# keyboard_main.net
KiCad netlist of a schematic drawn in Altium Designer
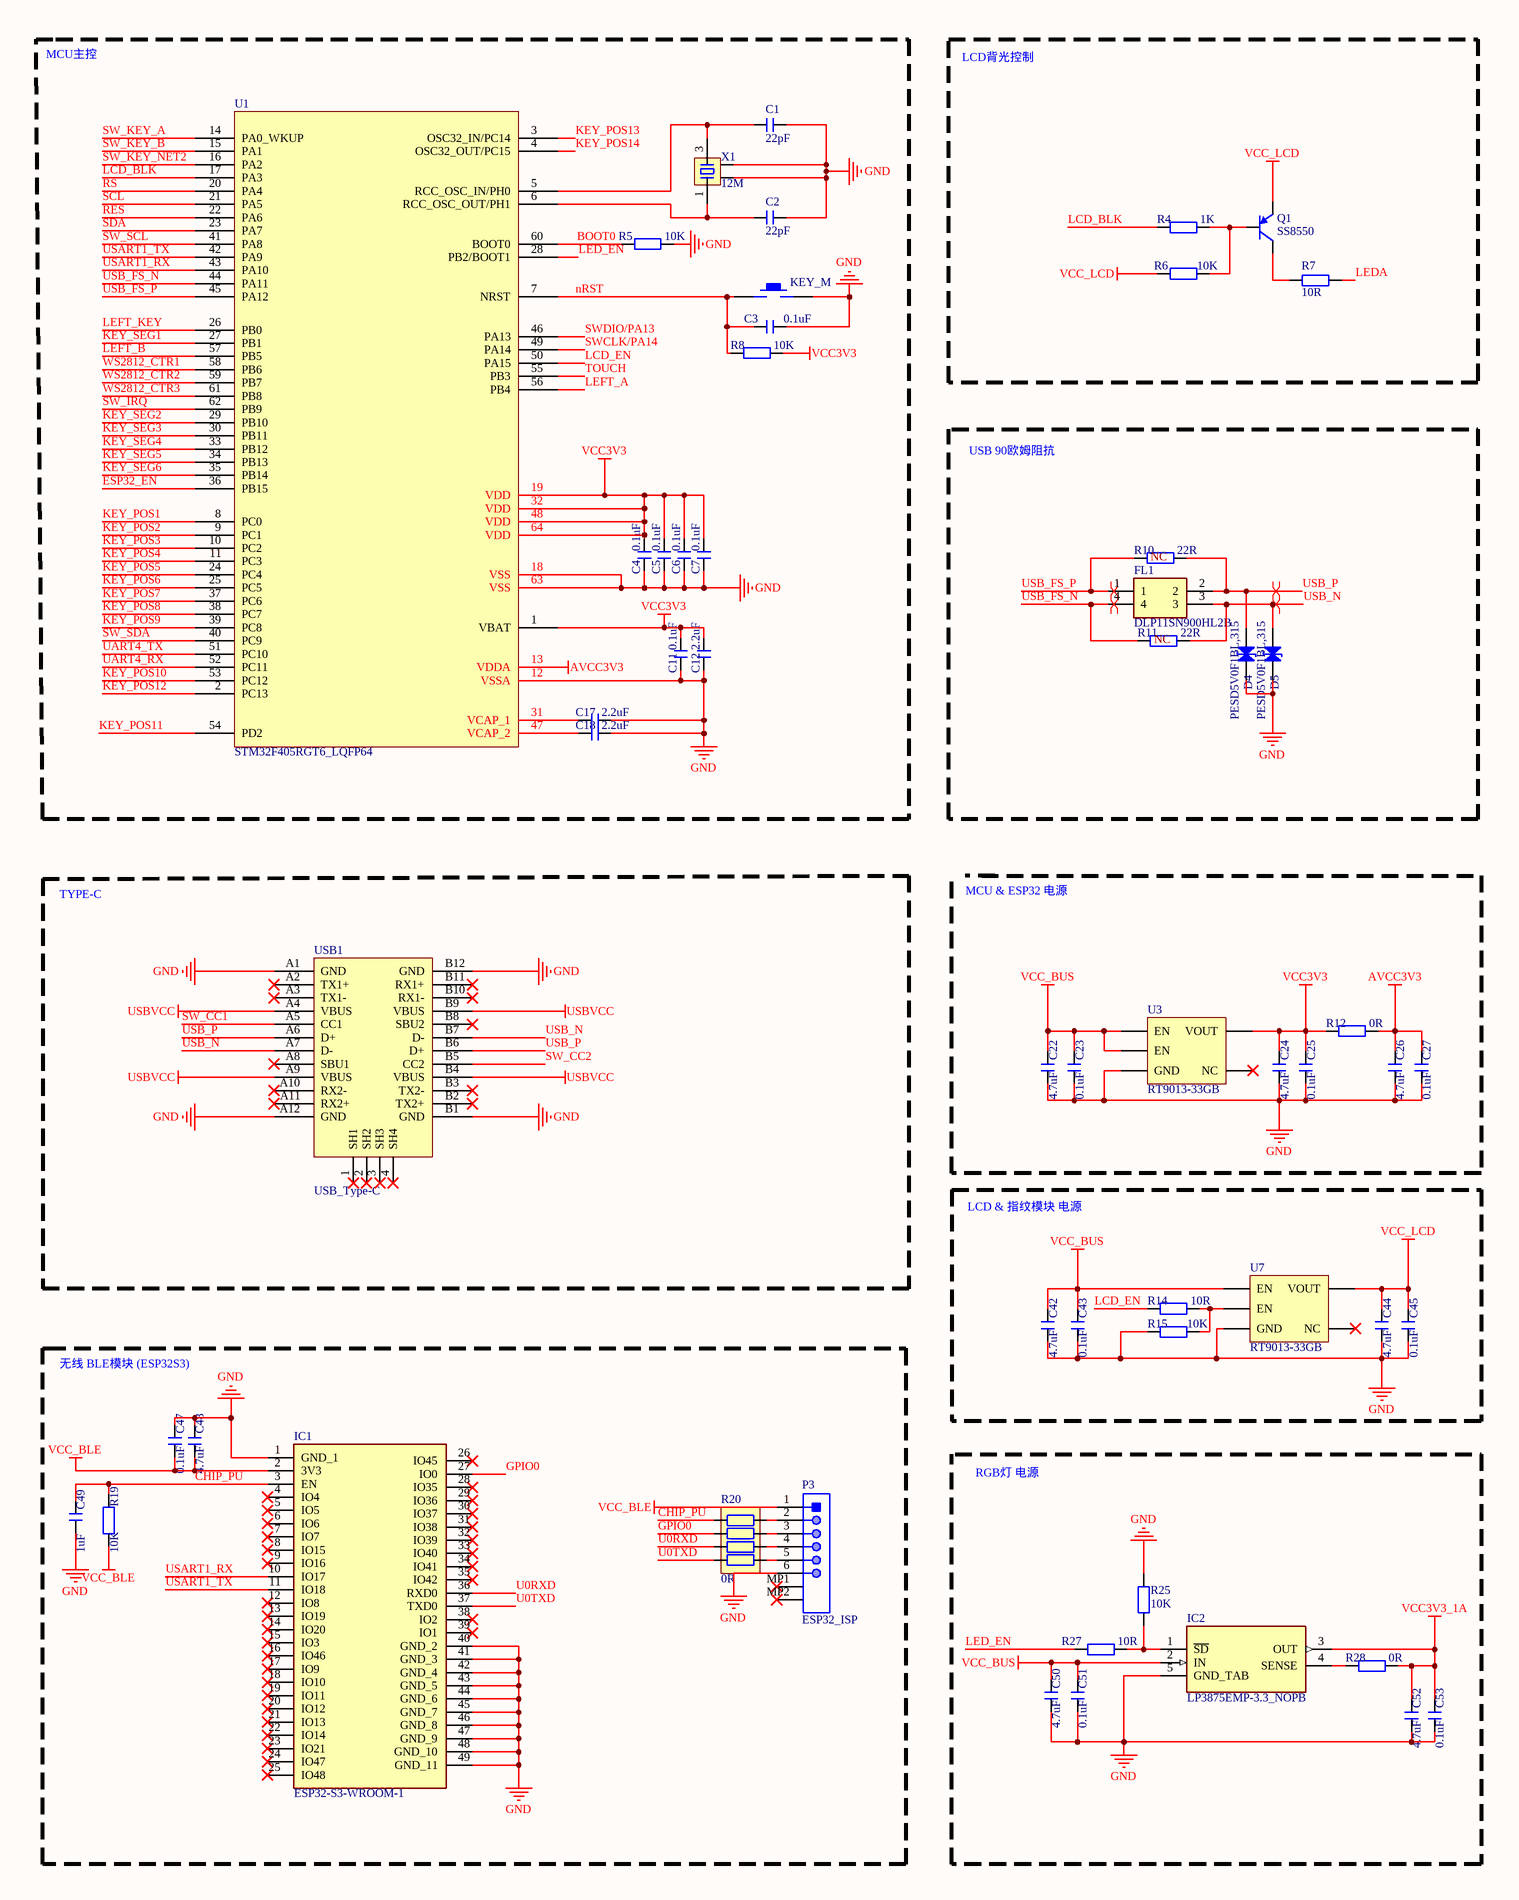
[diagram p0: keyboard_main.SchDoc, left]
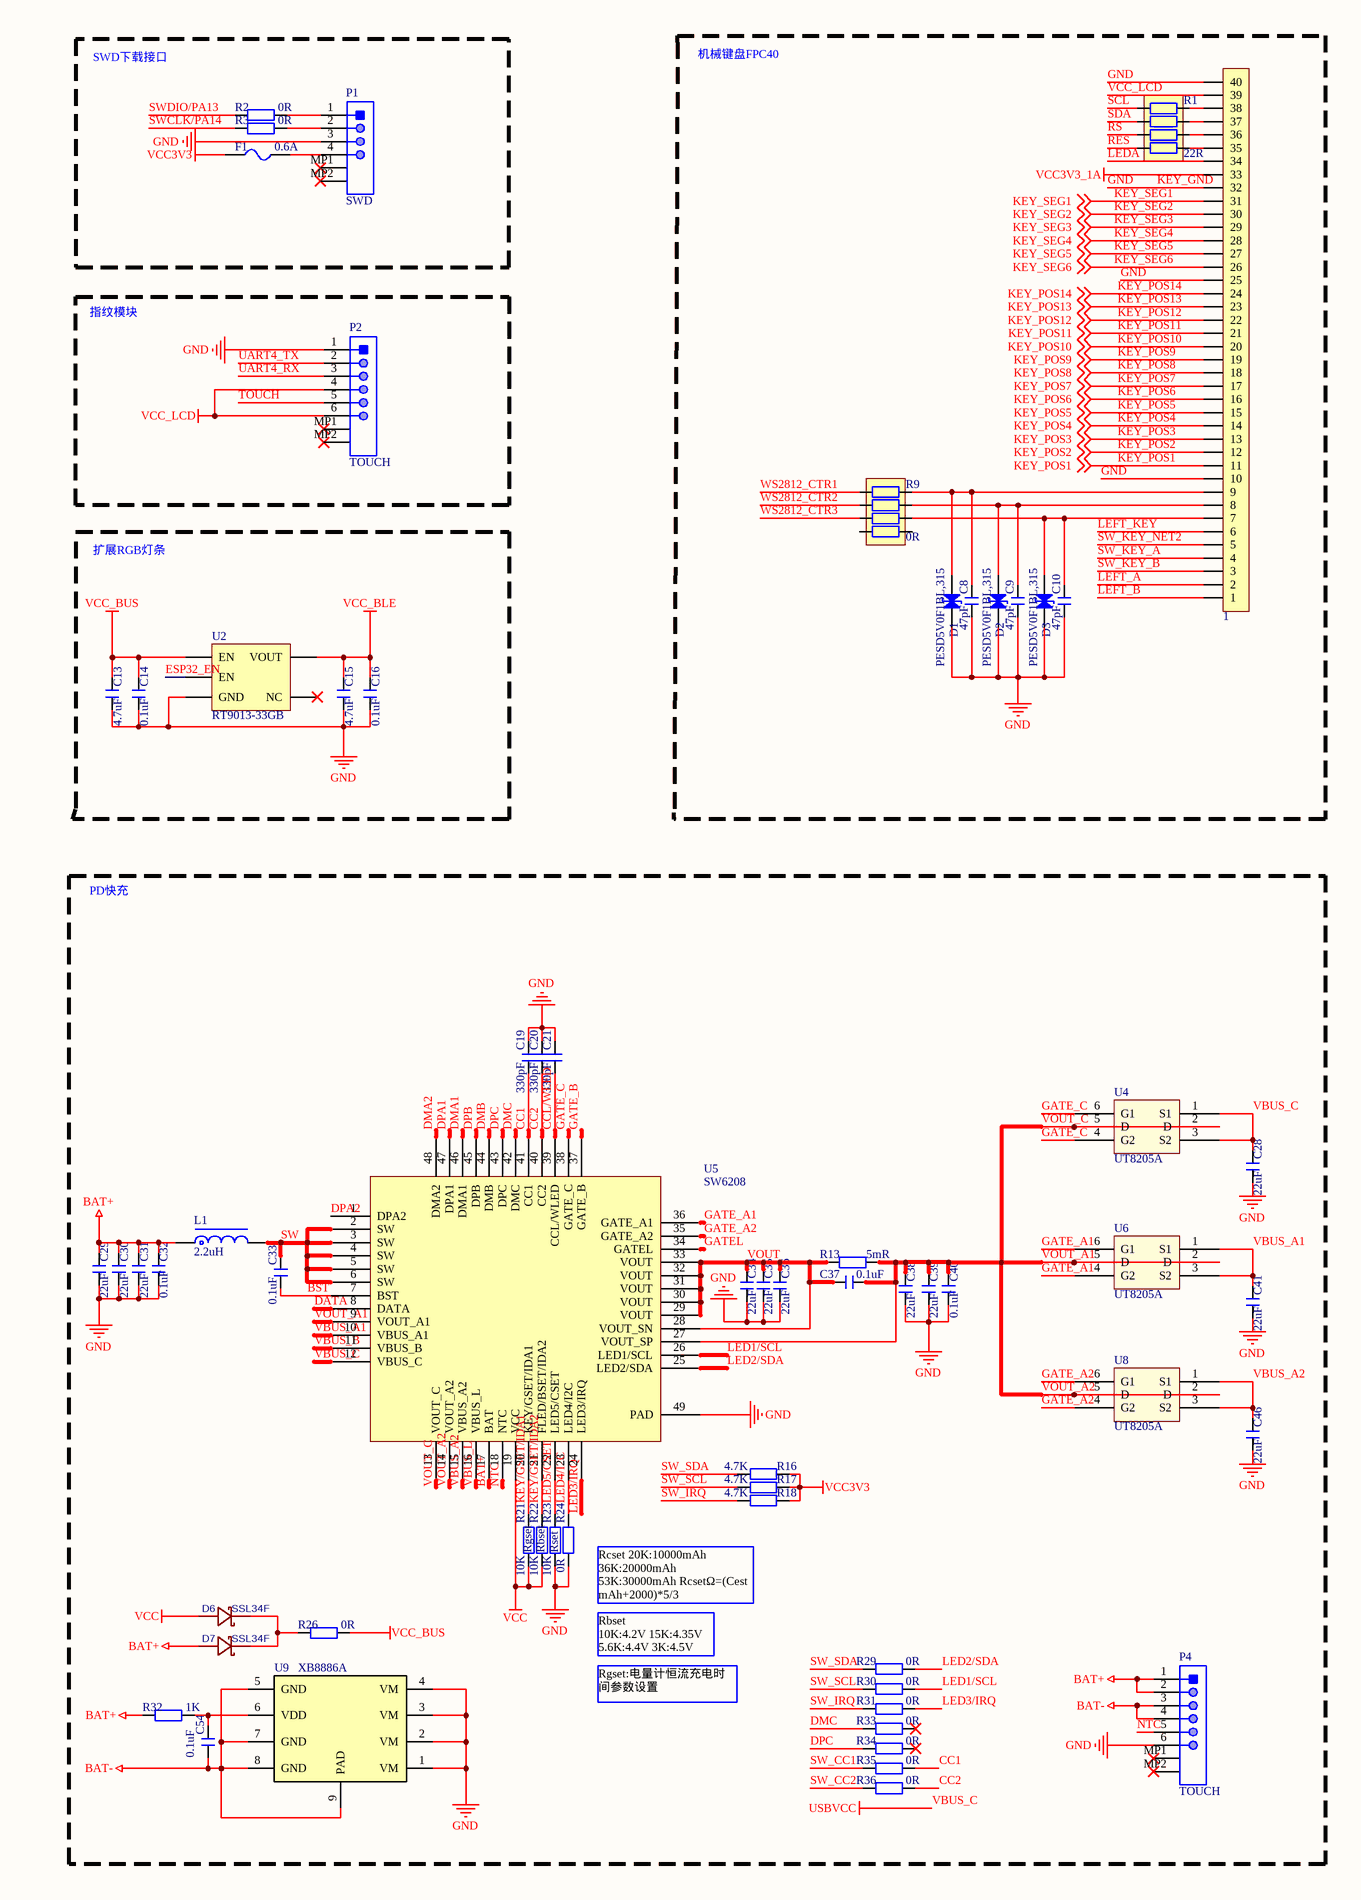
[diagram p1: keyboard_main.SchDoc, right]

(export (version "E")
  (design (tool "Eeschema 10.0.6"))
  (components
    (comp (ref "1")
      (value "FPC1.0-40P")
      (footprint "FPC0.5 2H-WS-40P")
      (description "FPC连接器")
      (fields (field (name "版权归属") "黎明电子style"))
      (libsource (lib "FPC连接器") (part "FPC-40P"))
    )
    (comp (ref "C1")
      (value "22pF")
      (footprint "C 0402_L")
      (description "贴片电容")
      (libsource (lib "0.1 - 电阻-电容-电感") (part "C"))
    )
    (comp (ref "C2")
      (value "22pF")
      (footprint "C 0402_L")
      (description "贴片电容")
      (libsource (lib "0.1 - 电阻-电容-电感") (part "C"))
    )
    (comp (ref "C3")
      (value "0.1uF")
      (footprint "C 0402_L")
      (description "贴片电容")
      (libsource (lib "0.1 - 电阻-电容-电感") (part "C"))
    )
    (comp (ref "C4")
      (value "0.1uF")
      (footprint "C 0402_L")
      (description "贴片电容")
      (libsource (lib "0.1 - 电阻-电容-电感") (part "C"))
    )
    (comp (ref "C5")
      (value "0.1uF")
      (footprint "C 0402_L")
      (description "贴片电容")
      (libsource (lib "0.1 - 电阻-电容-电感") (part "C"))
    )
    (comp (ref "C6")
      (value "0.1uF")
      (footprint "C 0402_L")
      (description "贴片电容")
      (libsource (lib "0.1 - 电阻-电容-电感") (part "C"))
    )
    (comp (ref "C7")
      (value "0.1uF")
      (footprint "C 0402_L")
      (description "贴片电容")
      (libsource (lib "0.1 - 电阻-电容-电感") (part "C"))
    )
    (comp (ref "C8")
      (value "47pF")
      (footprint "C 0402_L")
      (description "贴片电容")
      (libsource (lib "0.1 - 电阻-电容-电感") (part "C"))
    )
    (comp (ref "C9")
      (value "47pF")
      (footprint "C 0402_L")
      (description "贴片电容")
      (libsource (lib "0.1 - 电阻-电容-电感") (part "C"))
    )
    (comp (ref "C10")
      (value "47pF")
      (footprint "C 0402_L")
      (description "贴片电容")
      (libsource (lib "0.1 - 电阻-电容-电感") (part "C"))
    )
    (comp (ref "C11")
      (value "0.1uF")
      (footprint "C 0402_L")
      (description "贴片电容")
      (libsource (lib "0.1 - 电阻-电容-电感") (part "C"))
    )
    (comp (ref "C12")
      (value "2.2uF")
      (footprint "C 0402_L")
      (description "贴片电容")
      (libsource (lib "0.1 - 电阻-电容-电感") (part "C"))
    )
    (comp (ref "C13")
      (value "4.7uF")
      (footprint "C 0402_L")
      (description "贴片电容")
      (libsource (lib "0.1 - 电阻-电容-电感") (part "C"))
    )
    (comp (ref "C14")
      (value "0.1uF")
      (footprint "C 0402_L")
      (description "贴片电容")
      (libsource (lib "0.1 - 电阻-电容-电感") (part "C"))
    )
    (comp (ref "C15")
      (value "4.7uF")
      (footprint "C 0402_L")
      (description "贴片电容")
      (libsource (lib "0.1 - 电阻-电容-电感") (part "C"))
    )
    (comp (ref "C16")
      (value "0.1uF")
      (footprint "C 0402_L")
      (description "贴片电容")
      (libsource (lib "0.1 - 电阻-电容-电感") (part "C"))
    )
    (comp (ref "C17")
      (value "2.2uF")
      (footprint "C 0402_L")
      (description "贴片电容")
      (libsource (lib "0.1 - 电阻-电容-电感") (part "C"))
    )
    (comp (ref "C18")
      (value "2.2uF")
      (footprint "C 0402_L")
      (description "贴片电容")
      (libsource (lib "0.1 - 电阻-电容-电感") (part "C"))
    )
    (comp (ref "C19")
      (value "330pF")
      (footprint "C 0402_L")
      (description "贴片电容")
      (libsource (lib "0.1 - 电阻-电容-电感") (part "C"))
    )
    (comp (ref "C20")
      (value "330pF")
      (footprint "C 0402_L")
      (description "贴片电容")
      (libsource (lib "0.1 - 电阻-电容-电感") (part "C"))
    )
    (comp (ref "C21")
      (value "330pF")
      (footprint "C 0402_L")
      (description "贴片电容")
      (libsource (lib "0.1 - 电阻-电容-电感") (part "C"))
    )
    (comp (ref "C22")
      (value "4.7uF")
      (footprint "C 0402_L")
      (description "贴片电容")
      (libsource (lib "0.1 - 电阻-电容-电感") (part "C"))
    )
    (comp (ref "C23")
      (value "0.1uF")
      (footprint "C 0402_L")
      (description "贴片电容")
      (libsource (lib "0.1 - 电阻-电容-电感") (part "C"))
    )
    (comp (ref "C24")
      (value "4.7uF")
      (footprint "C 0402_L")
      (description "贴片电容")
      (libsource (lib "0.1 - 电阻-电容-电感") (part "C"))
    )
    (comp (ref "C25")
      (value "0.1uF")
      (footprint "C 0402_L")
      (description "贴片电容")
      (libsource (lib "0.1 - 电阻-电容-电感") (part "C"))
    )
    (comp (ref "C26")
      (value "4.7uF")
      (footprint "C 0402_L")
      (description "贴片电容")
      (libsource (lib "0.1 - 电阻-电容-电感") (part "C"))
    )
    (comp (ref "C27")
      (value "0.1uF")
      (footprint "C 0402_L")
      (description "贴片电容")
      (libsource (lib "0.1 - 电阻-电容-电感") (part "C"))
    )
    (comp (ref "C28")
      (value "22uF")
      (footprint "C 0805_L")
      (description "贴片电容")
      (libsource (lib "0.1 - 电阻-电容-电感") (part "C"))
    )
    (comp (ref "C29")
      (value "22uF")
      (footprint "C 0805_L")
      (description "贴片电容")
      (libsource (lib "0.1 - 电阻-电容-电感") (part "C"))
    )
    (comp (ref "C30")
      (value "22uF")
      (footprint "C 0805_L")
      (description "贴片电容")
      (libsource (lib "0.1 - 电阻-电容-电感") (part "C"))
    )
    (comp (ref "C31")
      (value "22uF")
      (footprint "C 0805_L")
      (description "贴片电容")
      (libsource (lib "0.1 - 电阻-电容-电感") (part "C"))
    )
    (comp (ref "C32")
      (value "0.1uF")
      (footprint "C 0805_L")
      (description "贴片电容")
      (libsource (lib "0.1 - 电阻-电容-电感") (part "C"))
    )
    (comp (ref "C33")
      (value "0.1uF")
      (footprint "C 0603_L")
      (description "贴片电容")
      (libsource (lib "0.1 - 电阻-电容-电感") (part "C"))
    )
    (comp (ref "C34")
      (value "22uF")
      (footprint "C 0805_L")
      (description "贴片电容")
      (libsource (lib "0.1 - 电阻-电容-电感") (part "C"))
    )
    (comp (ref "C35")
      (value "22uF")
      (footprint "C 0805_L")
      (description "贴片电容")
      (libsource (lib "0.1 - 电阻-电容-电感") (part "C"))
    )
    (comp (ref "C36")
      (value "22uF")
      (footprint "C 0805_L")
      (description "贴片电容")
      (libsource (lib "0.1 - 电阻-电容-电感") (part "C"))
    )
    (comp (ref "C37")
      (value "0.1uF")
      (footprint "C 0805_L")
      (description "贴片电容")
      (libsource (lib "0.1 - 电阻-电容-电感") (part "C"))
    )
    (comp (ref "C38")
      (value "22uF")
      (footprint "C 0805_L")
      (description "贴片电容")
      (libsource (lib "0.1 - 电阻-电容-电感") (part "C"))
    )
    (comp (ref "C39")
      (value "22uF")
      (footprint "C 0805_L")
      (description "贴片电容")
      (libsource (lib "0.1 - 电阻-电容-电感") (part "C"))
    )
    (comp (ref "C40")
      (value "0.1uF")
      (footprint "C 0805_L")
      (description "贴片电容")
      (libsource (lib "0.1 - 电阻-电容-电感") (part "C"))
    )
    (comp (ref "C41")
      (value "22uF")
      (footprint "C 0805_L")
      (description "贴片电容")
      (libsource (lib "0.1 - 电阻-电容-电感") (part "C"))
    )
    (comp (ref "C42")
      (value "4.7uF")
      (footprint "C 0402_L")
      (description "贴片电容")
      (libsource (lib "0.1 - 电阻-电容-电感") (part "C"))
    )
    (comp (ref "C43")
      (value "0.1uF")
      (footprint "C 0402_L")
      (description "贴片电容")
      (libsource (lib "0.1 - 电阻-电容-电感") (part "C"))
    )
    (comp (ref "C44")
      (value "4.7uF")
      (footprint "C 0402_L")
      (description "贴片电容")
      (libsource (lib "0.1 - 电阻-电容-电感") (part "C"))
    )
    (comp (ref "C45")
      (value "0.1uF")
      (footprint "C 0402_L")
      (description "贴片电容")
      (libsource (lib "0.1 - 电阻-电容-电感") (part "C"))
    )
    (comp (ref "C46")
      (value "22uF")
      (footprint "C 0805_L")
      (description "贴片电容")
      (libsource (lib "0.1 - 电阻-电容-电感") (part "C"))
    )
    (comp (ref "C47")
      (value "0.1uF")
      (footprint "C 0402_L")
      (description "贴片电容")
      (libsource (lib "0.1 - 电阻-电容-电感") (part "C"))
    )
    (comp (ref "C48")
      (value "4.7uF")
      (footprint "C 0402_L")
      (description "贴片电容")
      (libsource (lib "0.1 - 电阻-电容-电感") (part "C"))
    )
    (comp (ref "C49")
      (value "1uF")
      (footprint "C 0402_L")
      (description "贴片电容")
      (libsource (lib "0.1 - 电阻-电容-电感") (part "C"))
    )
    (comp (ref "C50")
      (value "4.7uF")
      (footprint "C 0402_L")
      (description "贴片电容")
      (libsource (lib "0.1 - 电阻-电容-电感") (part "C"))
    )
    (comp (ref "C51")
      (value "0.1uF")
      (footprint "C 0402_L")
      (description "贴片电容")
      (libsource (lib "0.1 - 电阻-电容-电感") (part "C"))
    )
    (comp (ref "C52")
      (value "4.7uF")
      (footprint "C 0402_L")
      (description "贴片电容")
      (libsource (lib "0.1 - 电阻-电容-电感") (part "C"))
    )
    (comp (ref "C53")
      (value "0.1uF")
      (footprint "C 0402_L")
      (description "贴片电容")
      (libsource (lib "0.1 - 电阻-电容-电感") (part "C"))
    )
    (comp (ref "C54")
      (value "0.1uF")
      (footprint "C 0805_L")
      (description "贴片电容")
      (libsource (lib "0.1 - 电阻-电容-电感") (part "C"))
    )
    (comp (ref "D1")
      (value "PESD5V0F1BL,315")
      (footprint "SOD-882_L1.0-W0.6-BI")
      (description "PESD5V0F1BL,315、ESD二极管、5.5V")
      (libsource (lib "0.2 -  二极管-整流桥") (part "PESD5V0F1BL,315"))
    )
    (comp (ref "D2")
      (value "PESD5V0F1BL,315")
      (footprint "SOD-882_L1.0-W0.6-BI")
      (description "PESD5V0F1BL,315、ESD二极管、5.5V")
      (libsource (lib "0.2 -  二极管-整流桥") (part "PESD5V0F1BL,315"))
    )
    (comp (ref "D3")
      (value "PESD5V0F1BL,315")
      (footprint "SOD-882_L1.0-W0.6-BI")
      (description "PESD5V0F1BL,315、ESD二极管、5.5V")
      (libsource (lib "0.2 -  二极管-整流桥") (part "PESD5V0F1BL,315"))
    )
    (comp (ref "D4")
      (value "PESD5V0F1BL,315")
      (footprint "SOD-882_L1.0-W0.6-BI")
      (description "PESD5V0F1BL,315、ESD二极管、5.5V")
      (libsource (lib "0.2 -  二极管-整流桥") (part "PESD5V0F1BL,315"))
    )
    (comp (ref "D5")
      (value "PESD5V0F1BL,315")
      (footprint "SOD-882_L1.0-W0.6-BI")
      (description "PESD5V0F1BL,315、ESD二极管、5.5V")
      (libsource (lib "0.2 -  二极管-整流桥") (part "PESD5V0F1BL,315"))
    )
    (comp (ref "D6")
      (value "SSL34F")
      (footprint "SMAF_L3.5-W2.6-LS4.7-RD")
      (fields (field (name "BOM_SUPPLIER PART") "C1884559") (field (name "CONTRIBUTOR") "LCSC"))
      (libsource (lib "mx_pcb_library") (part "SSL34F_C1884559"))
    )
    (comp (ref "D7")
      (value "SSL34F")
      (footprint "SMAF_L3.5-W2.6-LS4.7-RD")
      (fields (field (name "BOM_SUPPLIER PART") "C1884559") (field (name "CONTRIBUTOR") "LCSC"))
      (libsource (lib "mx_pcb_library") (part "SSL34F_C1884559"))
    )
    (comp (ref "F1")
      (value "0.6A")
      (footprint "FU 0402")
      (description "贴片保险丝")
      (libsource (lib "2.0 - 保险丝-晶振-光耦") (part "FU"))
    )
    (comp (ref "FL1")
      (value "DLP11SN900HL2B")
      (footprint "vSeasky:DLP11SA350HL2B")
      (description "Filter")
      (fields (field (name "MOUSER PART NUMBER") "81-DLP11SN900HL2B"))
      (libsource (lib "vSeasky") (part "DLP11SN900HL2B"))
    )
    (comp (ref "IC1")
      (value "ESP32-S3-WROOM-1")
      (footprint "mx_pcb_library:ESP32S3WROOM1")
      (description "Integrated Circuit")
      (libsource (lib "mx_pcb_library") (part "ESP32-S3-WROOM-1"))
    )
    (comp (ref "IC2")
      (value "LP3875EMP-3.3_NOPB")
      (footprint "mx_pcb_library:SOT150P700X180-5N")
      (description "Integrated Circuit")
      (fields
        (field (name "MANUFACTURER_PART_NUMBER") "LP3875EMP-3.3/NOPB")
        (field (name "MOUSER PART NUMBER") "926-LP3875EMP33NOPB")
      )
      (libsource (lib "mx_pcb_library") (part "LP3875EMP-3.3_NOPB"))
    )
    (comp (ref "L1")
      (value "2.2uH")
      (footprint "CD32")
      (description "CD系列贴片线绕功率电感")
      (libsource (lib "0.1 - 电阻-电容-电感") (part "L-SMD"))
    )
    (comp (ref "P1")
      (value "SWD")
      (footprint "JST-SM04B-SRSS-TB_V")
      (description "Male Header, Pitch 1 mm, 1 x 4 Position, Height 2.9 mm, -25 to 85 degC, RoHS, Tape and Reel")
      (fields (field (name "MANUFACTURER") "JST"))
      (libsource (lib "JST SH Connector") (part "SM04B-SRSS-TB(LF)(SN)"))
    )
    (comp (ref "P2")
      (value "TOUCH")
      (footprint "JST-SM06B-SRSS-TB_V")
      (description "Male Header, Pitch 1 mm, 1 x 6 Position, Height 2.9 mm, -25 to 85 degC, RoHS, Tape and Reel")
      (fields (field (name "MANUFACTURER") "JST"))
      (libsource (lib "JST SH Connector") (part "SM06B-SRSS-TB(LF)(SN)"))
    )
    (comp (ref "P3")
      (value "ESP32_ISP")
      (footprint "JST-SM06B-SRSS-TB_V")
      (description "Male Header, Pitch 1 mm, 1 x 6 Position, Height 2.9 mm, -25 to 85 degC, RoHS, Tape and Reel")
      (fields (field (name "MANUFACTURER") "JST"))
      (libsource (lib "JST SH Connector") (part "SM06B-SRSS-TB(LF)(SN)"))
    )
    (comp (ref "P4")
      (value "TOUCH")
      (footprint "JST-SM06B-SRSS-TB_V")
      (description "Male Header, Pitch 1 mm, 1 x 6 Position, Height 2.9 mm, -25 to 85 degC, RoHS, Tape and Reel")
      (fields (field (name "MANUFACTURER") "JST"))
      (libsource (lib "JST SH Connector") (part "SM06B-SRSS-TB(LF)(SN)"))
    )
    (comp (ref "Q1")
      (value "SS8550")
      (footprint "SOT23-3N")
      (description "高频放大-PNP型")
      (libsource (lib "0.4 - 三极管") (part "8550-SMD"))
    )
    (comp (ref "R1")
      (value "22R")
      (footprint "RCA-8P4R-0402")
      (description "贴片排阻")
      (libsource (lib "") (part "R-8P4R_1"))
    )
    (comp (ref "R2")
      (value "0R")
      (footprint "R 0402_L")
      (description "贴片电阻")
      (libsource (lib "0.1 - 电阻-电容-电感") (part "R"))
    )
    (comp (ref "R3")
      (value "0R")
      (footprint "R 0402_L")
      (description "贴片电阻")
      (libsource (lib "0.1 - 电阻-电容-电感") (part "R"))
    )
    (comp (ref "R4")
      (value "1K")
      (footprint "R 0402_L")
      (description "贴片电阻")
      (libsource (lib "0.1 - 电阻-电容-电感") (part "R"))
    )
    (comp (ref "R5")
      (value "10K")
      (footprint "R 0402_L")
      (description "贴片电阻")
      (libsource (lib "0.1 - 电阻-电容-电感") (part "R"))
    )
    (comp (ref "R6")
      (value "10K")
      (footprint "R 0402_L")
      (description "贴片电阻")
      (libsource (lib "0.1 - 电阻-电容-电感") (part "R"))
    )
    (comp (ref "R7")
      (value "10R")
      (footprint "R 0402_L")
      (description "贴片电阻")
      (libsource (lib "0.1 - 电阻-电容-电感") (part "R"))
    )
    (comp (ref "R8")
      (value "10K")
      (footprint "R 0402_L")
      (description "贴片电阻")
      (libsource (lib "0.1 - 电阻-电容-电感") (part "R"))
    )
    (comp (ref "R9")
      (value "0R")
      (footprint "RCA-8P4R-0402")
      (description "贴片排阻")
      (libsource (lib "") (part "R-8P4R_1"))
    )
    (comp (ref "R10")
      (value "22R")
      (footprint "R 0402_L")
      (description "贴片电阻")
      (libsource (lib "0.1 - 电阻-电容-电感") (part "R"))
    )
    (comp (ref "R11")
      (value "22R")
      (footprint "R 0402_L")
      (description "贴片电阻")
      (libsource (lib "0.1 - 电阻-电容-电感") (part "R"))
    )
    (comp (ref "R12")
      (value "0R")
      (footprint "R 0402_L")
      (description "贴片电阻")
      (libsource (lib "0.1 - 电阻-电容-电感") (part "R"))
    )
    (comp (ref "R13")
      (value "5mR")
      (footprint "R 1206_L")
      (description "贴片电阻")
      (libsource (lib "0.1 - 电阻-电容-电感") (part "R"))
    )
    (comp (ref "R14")
      (value "10R")
      (footprint "R 0402_L")
      (description "贴片电阻")
      (libsource (lib "0.1 - 电阻-电容-电感") (part "R"))
    )
    (comp (ref "R15")
      (value "10K")
      (footprint "R 0402_L")
      (description "贴片电阻")
      (libsource (lib "0.1 - 电阻-电容-电感") (part "R"))
    )
    (comp (ref "R16")
      (value "4.7K")
      (footprint "R 0402_L")
      (description "贴片电阻")
      (libsource (lib "0.1 - 电阻-电容-电感") (part "R"))
    )
    (comp (ref "R17")
      (value "4.7K")
      (footprint "R 0402_L")
      (description "贴片电阻")
      (libsource (lib "0.1 - 电阻-电容-电感") (part "R"))
    )
    (comp (ref "R18")
      (value "4.7K")
      (footprint "R 0402_L")
      (description "贴片电阻")
      (libsource (lib "0.1 - 电阻-电容-电感") (part "R"))
    )
    (comp (ref "R19")
      (value "10K")
      (footprint "R 0402_L")
      (description "贴片电阻")
      (libsource (lib "0.1 - 电阻-电容-电感") (part "R"))
    )
    (comp (ref "R20")
      (value "0R")
      (footprint "RCA-8P4R-0402")
      (description "贴片排阻")
      (libsource (lib "0.1 - 电阻-电容-电感") (part "R-8P4R"))
    )
    (comp (ref "R21")
      (value "10K")
      (footprint "R 0402_L")
      (description "贴片电阻")
      (libsource (lib "0.1 - 电阻-电容-电感") (part "R"))
    )
    (comp (ref "R22")
      (value "10K")
      (footprint "R 0402_L")
      (description "贴片电阻")
      (libsource (lib "0.1 - 电阻-电容-电感") (part "R"))
    )
    (comp (ref "R23")
      (value "10K")
      (footprint "R 0402_L")
      (description "贴片电阻")
      (libsource (lib "0.1 - 电阻-电容-电感") (part "R"))
    )
    (comp (ref "R24")
      (value "0R")
      (footprint "R 0402_L")
      (description "贴片电阻")
      (libsource (lib "0.1 - 电阻-电容-电感") (part "R"))
    )
    (comp (ref "R25")
      (value "10K")
      (footprint "R 0402_L")
      (description "贴片电阻")
      (libsource (lib "0.1 - 电阻-电容-电感") (part "R"))
    )
    (comp (ref "R26")
      (value "0R")
      (footprint "R 0402_L")
      (description "贴片电阻")
      (libsource (lib "0.1 - 电阻-电容-电感") (part "R"))
    )
    (comp (ref "R27")
      (value "10R")
      (footprint "R 0402_L")
      (description "贴片电阻")
      (libsource (lib "0.1 - 电阻-电容-电感") (part "R"))
    )
    (comp (ref "R28")
      (value "0R")
      (footprint "R 0402_L")
      (description "贴片电阻")
      (libsource (lib "0.1 - 电阻-电容-电感") (part "R"))
    )
    (comp (ref "R29")
      (value "0R")
      (footprint "R 0402_L")
      (description "贴片电阻")
      (libsource (lib "0.1 - 电阻-电容-电感") (part "R"))
    )
    (comp (ref "R30")
      (value "0R")
      (footprint "R 0402_L")
      (description "贴片电阻")
      (libsource (lib "0.1 - 电阻-电容-电感") (part "R"))
    )
    (comp (ref "R31")
      (value "0R")
      (footprint "R 0402_L")
      (description "贴片电阻")
      (libsource (lib "0.1 - 电阻-电容-电感") (part "R"))
    )
    (comp (ref "R32")
      (value "1K")
      (footprint "R 0402_L")
      (description "贴片电阻")
      (libsource (lib "0.1 - 电阻-电容-电感") (part "R"))
    )
    (comp (ref "R33")
      (value "0R")
      (footprint "R 0402_L")
      (description "贴片电阻")
      (libsource (lib "0.1 - 电阻-电容-电感") (part "R"))
    )
    (comp (ref "R34")
      (value "0R")
      (footprint "R 0402_L")
      (description "贴片电阻")
      (libsource (lib "0.1 - 电阻-电容-电感") (part "R"))
    )
    (comp (ref "R35")
      (value "0R")
      (footprint "R 0402_L")
      (description "贴片电阻")
      (libsource (lib "0.1 - 电阻-电容-电感") (part "R"))
    )
    (comp (ref "R36")
      (value "0R")
      (footprint "R 0402_L")
      (description "贴片电阻")
      (libsource (lib "0.1 - 电阻-电容-电感") (part "R"))
    )
    (comp (ref "RST1")
      (value "KEY_M")
      (footprint "SMD-3.2*4.2")
      (libsource (lib "mx_pcb_library") (part "KEY_M"))
    )
    (comp (ref "U1")
      (value "STM32F405RGT6_LQFP64")
      (footprint "LQFP-64_10X10X05P")
      (libsource (lib "mx_pcb_library") (part "STM32F405RGT6_LQFP64"))
    )
    (comp (ref "U2")
      (value "RT9013-33GB")
      (footprint "SOT23-5M")
      (libsource (lib "mx_pcb_library") (part "RT9013-33GB"))
    )
    (comp (ref "U3")
      (value "RT9013-33GB")
      (footprint "SOT23-5M")
      (libsource (lib "mx_pcb_library") (part "RT9013-33GB"))
    )
    (comp (ref "U4")
      (value "UT8205A")
      (footprint "mx_pcb_library:SOT23-6")
      (libsource (lib "mx_pcb_library") (part "UT8205A"))
    )
    (comp (ref "U5")
      (value "SW6208")
      (footprint "QFN-48_6x6")
      (description "充电宝芯片")
      (libsource (lib "mx_pcb_library") (part "SW6208"))
    )
    (comp (ref "U6")
      (value "UT8205A")
      (footprint "mx_pcb_library:SOT23-6")
      (libsource (lib "mx_pcb_library") (part "UT8205A"))
    )
    (comp (ref "U7")
      (value "RT9013-33GB")
      (footprint "SOT23-5M")
      (libsource (lib "mx_pcb_library") (part "RT9013-33GB"))
    )
    (comp (ref "U8")
      (value "UT8205A")
      (footprint "mx_pcb_library:SOT23-6")
      (libsource (lib "mx_pcb_library") (part "UT8205A"))
    )
    (comp (ref "U9")
      (value "XB8886A")
      (footprint "mx_pcb_library:SO-8-PAD")
      (fields (field (name "MF") "Texas Instruments") (field (name "MP") "NE5532D"))
      (libsource (lib "mx_pcb_library") (part "XB8886A"))
    )
    (comp (ref "USB1")
      (value "USB_Type-C")
      (footprint "Type-C-TOP")
      (libsource (lib "mx_pcb_library") (part "USB_Type-C"))
    )
    (comp (ref "X1")
      (value "12M")
      (footprint "OSC 3225-4P")
      (description "4脚无源晶振")
      (libsource (lib "2.0 - 保险丝-晶振-光耦") (part "XTAL-4P"))
    )
  )
  (nets
    (net (code "1") (name "/BOOT0") (class "Default")
      (node (ref "R5") (pin "1") (pinfunction "1_1") (pintype "passive"))
      (node (ref "U1") (pin "60") (pinfunction "BOOT0_60") (pintype "passive"))
    )
    (net (code "2") (name "/BST") (class "Default")
      (node (ref "C33") (pin "1") (pinfunction "1_1") (pintype "passive"))
      (node (ref "U5") (pin "7") (pinfunction "BST_7") (pintype "passive"))
    )
    (net (code "3") (name "/CC1") (class "Default")
      (node (ref "C19") (pin "1") (pinfunction "1_1") (pintype "passive"))
      (node (ref "R35") (pin "2") (pinfunction "2_2") (pintype "passive"))
      (node (ref "U5") (pin "41") (pinfunction "CC1_41") (pintype "passive"))
    )
    (net (code "4") (name "/CC2") (class "Default")
      (node (ref "C20") (pin "1") (pinfunction "1_1") (pintype "passive"))
      (node (ref "R36") (pin "2") (pinfunction "2_2") (pintype "passive"))
      (node (ref "U5") (pin "40") (pinfunction "CC2_40") (pintype "passive"))
    )
    (net (code "5") (name "/CCL{slash}WLED") (class "Default")
      (node (ref "C21") (pin "1") (pinfunction "1_1") (pintype "passive"))
      (node (ref "U5") (pin "39") (pinfunction "CCL/WLED_39") (pintype "passive"))
    )
    (net (code "6") (name "/CHIP_PU") (class "Default")
      (node (ref "C49") (pin "1") (pinfunction "1_1") (pintype "passive"))
      (node (ref "IC1") (pin "3") (pinfunction "EN_3") (pintype "passive"))
      (node (ref "R19") (pin "1") (pinfunction "1_1") (pintype "passive"))
      (node (ref "R20") (pin "8") (pinfunction "8_8") (pintype "passive"))
    )
    (net (code "7") (name "/DATA") (class "Default")
      (node (ref "U5") (pin "8") (pinfunction "DATA_8") (pintype "passive"))
    )
    (net (code "8") (name "/DMA1") (class "Default")
      (node (ref "U5") (pin "46") (pinfunction "DMA1_46") (pintype "passive"))
    )
    (net (code "9") (name "/DMA2") (class "Default")
      (node (ref "U5") (pin "48") (pinfunction "DMA2_48") (pintype "passive"))
    )
    (net (code "10") (name "/DMB") (class "Default")
      (node (ref "U5") (pin "44") (pinfunction "DMB_44") (pintype "passive"))
    )
    (net (code "11") (name "/DMC") (class "Default")
      (node (ref "R33") (pin "1") (pinfunction "1_1") (pintype "passive"))
      (node (ref "U5") (pin "42") (pinfunction "DMC_42") (pintype "passive"))
    )
    (net (code "12") (name "/DPA1") (class "Default")
      (node (ref "U5") (pin "47") (pinfunction "DPA1_47") (pintype "passive"))
    )
    (net (code "13") (name "/DPA2") (class "Default")
      (node (ref "U5") (pin "1") (pinfunction "DPA2_1") (pintype "passive"))
    )
    (net (code "14") (name "/DPB") (class "Default")
      (node (ref "U5") (pin "45") (pinfunction "DPB_45") (pintype "passive"))
    )
    (net (code "15") (name "/DPC") (class "Default")
      (node (ref "R34") (pin "1") (pinfunction "1_1") (pintype "passive"))
      (node (ref "U5") (pin "43") (pinfunction "DPC_43") (pintype "passive"))
    )
    (net (code "16") (name "/ESP32_EN") (class "Default")
      (node (ref "U1") (pin "36") (pinfunction "PB15_36") (pintype "passive"))
      (node (ref "U2") (pin "3") (pinfunction "EN_3") (pintype "passive"))
    )
    (net (code "17") (name "/GATEL") (class "Default")
      (node (ref "U5") (pin "34") (pinfunction "GATEL_34") (pintype "passive"))
    )
    (net (code "18") (name "/GATE_A1") (class "Default")
      (node (ref "U5") (pin "36") (pinfunction "GATE_A1_36") (pintype "passive"))
      (node (ref "U6") (pin "4") (pinfunction "G2_4") (pintype "passive"))
      (node (ref "U6") (pin "6") (pinfunction "G1_6") (pintype "passive"))
    )
    (net (code "19") (name "/GATE_A2") (class "Default")
      (node (ref "U5") (pin "35") (pinfunction "GATE_A2_35") (pintype "passive"))
      (node (ref "U8") (pin "4") (pinfunction "G2_4") (pintype "passive"))
      (node (ref "U8") (pin "6") (pinfunction "G1_6") (pintype "passive"))
    )
    (net (code "20") (name "/GATE_B") (class "Default")
      (node (ref "U5") (pin "37") (pinfunction "GATE_B_37") (pintype "passive"))
    )
    (net (code "21") (name "/GATE_C") (class "Default")
      (node (ref "U4") (pin "4") (pinfunction "G2_4") (pintype "passive"))
      (node (ref "U4") (pin "6") (pinfunction "G1_6") (pintype "passive"))
      (node (ref "U5") (pin "38") (pinfunction "GATE_C_38") (pintype "passive"))
    )
    (net (code "22") (name "/GPIO0") (class "Default")
      (node (ref "IC1") (pin "27") (pinfunction "IO0_27") (pintype "passive"))
      (node (ref "R20") (pin "7") (pinfunction "7_7") (pintype "passive"))
    )
    (net (code "23") (name "/KEY{slash}GSET{slash}IDA1") (class "Default")
      (node (ref "R21") (pin "1") (pinfunction "1_1") (pintype "passive"))
      (node (ref "U5") (pin "20") (pinfunction "KEY/GSET/IDA1_20") (pintype "passive"))
    )
    (net (code "24") (name "/KEY{slash}GSET{slash}IDA2") (class "Default")
      (node (ref "R22") (pin "1") (pinfunction "1_1") (pintype "passive"))
      (node (ref "U5") (pin "21") (pinfunction "FLED/BSET/IDA2_21") (pintype "passive"))
    )
    (net (code "25") (name "/LCD_BLK") (class "Default")
      (node (ref "R4") (pin "1") (pinfunction "1_1") (pintype "passive"))
      (node (ref "U1") (pin "17") (pinfunction "PA3_17") (pintype "passive"))
    )
    (net (code "26") (name "/LCD_EN") (class "Default")
      (node (ref "R14") (pin "1") (pinfunction "1_1") (pintype "passive"))
      (node (ref "U1") (pin "50") (pinfunction "PA15_50") (pintype "passive"))
    )
    (net (code "27") (name "/LED1{slash}SCL") (class "Default")
      (node (ref "R30") (pin "2") (pinfunction "2_2") (pintype "passive"))
      (node (ref "U5") (pin "26") (pinfunction "LED1/SCL_26") (pintype "passive"))
    )
    (net (code "28") (name "/LED2{slash}SDA") (class "Default")
      (node (ref "R29") (pin "2") (pinfunction "2_2") (pintype "passive"))
      (node (ref "U5") (pin "25") (pinfunction "LED2/SDA_25") (pintype "passive"))
    )
    (net (code "29") (name "/LED3{slash}IRQ") (class "Default")
      (node (ref "R31") (pin "2") (pinfunction "2_2") (pintype "passive"))
      (node (ref "U5") (pin "24") (pinfunction "LED3/IRQ_24") (pintype "passive"))
    )
    (net (code "30") (name "/LED4{slash}I2C") (class "Default")
      (node (ref "R24") (pin "1") (pinfunction "1_1") (pintype "passive"))
      (node (ref "U5") (pin "23") (pinfunction "LED4/I2C_23") (pintype "passive"))
    )
    (net (code "31") (name "/LED5{slash}CSET") (class "Default")
      (node (ref "R23") (pin "1") (pinfunction "1_1") (pintype "passive"))
      (node (ref "U5") (pin "22") (pinfunction "LED5/CSET_22") (pintype "passive"))
    )
    (net (code "32") (name "/LEDA") (class "Default")
      (node (ref "1") (pin "34") (pinfunction "34_34") (pintype "passive"))
      (node (ref "R7") (pin "1") (pinfunction "1_1") (pintype "passive"))
    )
    (net (code "33") (name "/LED_EN") (class "Default")
      (node (ref "R27") (pin "1") (pinfunction "1_1") (pintype "passive"))
      (node (ref "U1") (pin "28") (pinfunction "PB2/BOOT1_28") (pintype "passive"))
    )
    (net (code "34") (name "/LEFT_A") (class "Default")
      (node (ref "1") (pin "2") (pinfunction "2_2") (pintype "passive"))
      (node (ref "U1") (pin "56") (pinfunction "PB4_56") (pintype "passive"))
    )
    (net (code "35") (name "/LEFT_B") (class "Default")
      (node (ref "1") (pin "1") (pinfunction "1_1") (pintype "passive"))
      (node (ref "U1") (pin "57") (pinfunction "PB5_57") (pintype "passive"))
    )
    (net (code "36") (name "/LEFT_KEY") (class "Default")
      (node (ref "1") (pin "6") (pinfunction "6_6") (pintype "passive"))
      (node (ref "U1") (pin "26") (pinfunction "PB0_26") (pintype "passive"))
    )
    (net (code "37") (name "/NTC") (class "Default")
      (node (ref "P4") (pin "5") (pinfunction "5_5") (pintype "passive"))
      (node (ref "U5") (pin "18") (pinfunction "NTC_18") (pintype "passive"))
    )
    (net (code "38") (name "/RES") (class "Default")
      (node (ref "R1") (pin "4") (pinfunction "4_4") (pintype "passive"))
      (node (ref "U1") (pin "22") (pinfunction "PA6_22") (pintype "passive"))
    )
    (net (code "39") (name "/RS") (class "Default")
      (node (ref "R1") (pin "3") (pinfunction "3_3") (pintype "passive"))
      (node (ref "U1") (pin "20") (pinfunction "PA4_20") (pintype "passive"))
    )
    (net (code "40") (name "/SCL") (class "Default")
      (node (ref "R1") (pin "1") (pinfunction "1_1") (pintype "passive"))
      (node (ref "U1") (pin "21") (pinfunction "PA5_21") (pintype "passive"))
    )
    (net (code "41") (name "/SDA") (class "Default")
      (node (ref "R1") (pin "2") (pinfunction "2_2") (pintype "passive"))
      (node (ref "U1") (pin "23") (pinfunction "PA7_23") (pintype "passive"))
    )
    (net (code "42") (name "/SW") (class "Default")
      (node (ref "C33") (pin "2") (pinfunction "2_2") (pintype "passive"))
      (node (ref "L1") (pin "2") (pinfunction "2_2") (pintype "passive"))
      (node (ref "U5") (pin "2") (pinfunction "SW_2") (pintype "passive"))
      (node (ref "U5") (pin "3") (pinfunction "SW_3") (pintype "passive"))
      (node (ref "U5") (pin "4") (pinfunction "SW_4") (pintype "passive"))
      (node (ref "U5") (pin "5") (pinfunction "SW_5") (pintype "passive"))
      (node (ref "U5") (pin "6") (pinfunction "SW_6") (pintype "passive"))
    )
    (net (code "43") (name "/SWCLK{slash}PA14") (class "Default")
      (node (ref "R3") (pin "1") (pinfunction "1_1") (pintype "passive"))
      (node (ref "U1") (pin "49") (pinfunction "PA14_49") (pintype "passive"))
    )
    (net (code "44") (name "/SWDIO{slash}PA13") (class "Default")
      (node (ref "R2") (pin "1") (pinfunction "1_1") (pintype "passive"))
      (node (ref "U1") (pin "46") (pinfunction "PA13_46") (pintype "passive"))
    )
    (net (code "45") (name "/SW_CC1") (class "Default")
      (node (ref "R35") (pin "1") (pinfunction "1_1") (pintype "passive"))
      (node (ref "USB1") (pin "A5") (pinfunction "CC1_A5") (pintype "passive"))
    )
    (net (code "46") (name "/SW_CC2") (class "Default")
      (node (ref "R36") (pin "1") (pinfunction "1_1") (pintype "passive"))
      (node (ref "USB1") (pin "B5") (pinfunction "CC2_B5") (pintype "passive"))
    )
    (net (code "47") (name "/SW_IRQ") (class "Default")
      (node (ref "R18") (pin "2") (pinfunction "2_2") (pintype "passive"))
      (node (ref "R31") (pin "1") (pinfunction "1_1") (pintype "passive"))
      (node (ref "U1") (pin "62") (pinfunction "PB9_62") (pintype "passive"))
    )
    (net (code "48") (name "/SW_KEY_A") (class "Default")
      (node (ref "1") (pin "4") (pinfunction "4_4") (pintype "passive"))
      (node (ref "U1") (pin "14") (pinfunction "PA0_WKUP_14") (pintype "passive"))
    )
    (net (code "49") (name "/SW_KEY_B") (class "Default")
      (node (ref "1") (pin "3") (pinfunction "3_3") (pintype "passive"))
      (node (ref "U1") (pin "15") (pinfunction "PA1_15") (pintype "passive"))
    )
    (net (code "50") (name "/SW_KEY_NET2") (class "Default")
      (node (ref "1") (pin "5") (pinfunction "5_5") (pintype "passive"))
      (node (ref "U1") (pin "16") (pinfunction "PA2_16") (pintype "passive"))
    )
    (net (code "51") (name "/SW_SCL") (class "Default")
      (node (ref "R17") (pin "2") (pinfunction "2_2") (pintype "passive"))
      (node (ref "R30") (pin "1") (pinfunction "1_1") (pintype "passive"))
      (node (ref "U1") (pin "41") (pinfunction "PA8_41") (pintype "passive"))
    )
    (net (code "52") (name "/SW_SDA") (class "Default")
      (node (ref "R16") (pin "2") (pinfunction "2_2") (pintype "passive"))
      (node (ref "R29") (pin "1") (pinfunction "1_1") (pintype "passive"))
      (node (ref "U1") (pin "40") (pinfunction "PC9_40") (pintype "passive"))
    )
    (net (code "53") (name "/TOUCH") (class "Default")
      (node (ref "P2") (pin "5") (pinfunction "5_5") (pintype "passive"))
      (node (ref "U1") (pin "55") (pinfunction "PB3_55") (pintype "passive"))
    )
    (net (code "54") (name "/U0RXD") (class "Default")
      (node (ref "IC1") (pin "36") (pinfunction "RXD0_36") (pintype "passive"))
      (node (ref "R20") (pin "6") (pinfunction "6_6") (pintype "passive"))
    )
    (net (code "55") (name "/U0TXD") (class "Default")
      (node (ref "IC1") (pin "37") (pinfunction "TXD0_37") (pintype "passive"))
      (node (ref "R20") (pin "5") (pinfunction "5_5") (pintype "passive"))
    )
    (net (code "56") (name "/UART4_RX") (class "Default")
      (node (ref "P2") (pin "3") (pinfunction "3_3") (pintype "passive"))
      (node (ref "U1") (pin "52") (pinfunction "PC11_52") (pintype "passive"))
    )
    (net (code "57") (name "/UART4_TX") (class "Default")
      (node (ref "P2") (pin "2") (pinfunction "2_2") (pintype "passive"))
      (node (ref "U1") (pin "51") (pinfunction "PC10_51") (pintype "passive"))
    )
    (net (code "58") (name "/USART1_RX") (class "Default")
      (node (ref "IC1") (pin "10") (pinfunction "IO17_10") (pintype "passive"))
      (node (ref "U1") (pin "43") (pinfunction "PA10_43") (pintype "passive"))
    )
    (net (code "59") (name "/USART1_TX") (class "Default")
      (node (ref "IC1") (pin "11") (pinfunction "IO18_11") (pintype "passive"))
      (node (ref "U1") (pin "42") (pinfunction "PA9_42") (pintype "passive"))
    )
    (net (code "60") (name "/USB_FS_N") (class "Default")
      (node (ref "FL1") (pin "4") (pinfunction "4_4") (pintype "passive"))
      (node (ref "R11") (pin "1") (pinfunction "1_1") (pintype "passive"))
      (node (ref "U1") (pin "44") (pinfunction "PA11_44") (pintype "passive"))
    )
    (net (code "61") (name "/USB_FS_P") (class "Default")
      (node (ref "FL1") (pin "1") (pinfunction "1_1") (pintype "passive"))
      (node (ref "R10") (pin "1") (pinfunction "1_1") (pintype "passive"))
      (node (ref "U1") (pin "45") (pinfunction "PA12_45") (pintype "passive"))
    )
    (net (code "62") (name "/USB_N") (class "Default")
      (node (ref "D5") (pin "1") (pinfunction "A_1") (pintype "passive"))
      (node (ref "FL1") (pin "3") (pinfunction "3_3") (pintype "passive"))
      (node (ref "R11") (pin "2") (pinfunction "2_2") (pintype "passive"))
      (node (ref "USB1") (pin "A7") (pinfunction "D-_A7") (pintype "passive"))
      (node (ref "USB1") (pin "B7") (pinfunction "D-_B7") (pintype "passive"))
    )
    (net (code "63") (name "/USB_P") (class "Default")
      (node (ref "D4") (pin "1") (pinfunction "A_1") (pintype "passive"))
      (node (ref "FL1") (pin "2") (pinfunction "2_2") (pintype "passive"))
      (node (ref "R10") (pin "2") (pinfunction "2_2") (pintype "passive"))
      (node (ref "USB1") (pin "A6") (pinfunction "D+_A6") (pintype "passive"))
      (node (ref "USB1") (pin "B6") (pinfunction "D+_B6") (pintype "passive"))
    )
    (net (code "64") (name "/VBUS_A1") (class "Default")
      (node (ref "C41") (pin "2") (pinfunction "2_2") (pintype "passive"))
      (node (ref "U5") (pin "10") (pinfunction "VBUS_A1_10") (pintype "passive"))
      (node (ref "U6") (pin "1") (pinfunction "S1_1") (pintype "passive"))
      (node (ref "U6") (pin "3") (pinfunction "S2_3") (pintype "passive"))
    )
    (net (code "65") (name "/VBUS_A2") (class "Default")
      (node (ref "C46") (pin "2") (pinfunction "2_2") (pintype "passive"))
      (node (ref "U5") (pin "15") (pinfunction "VBUS_A2_15") (pintype "passive"))
      (node (ref "U8") (pin "1") (pinfunction "S1_1") (pintype "passive"))
      (node (ref "U8") (pin "3") (pinfunction "S2_3") (pintype "passive"))
    )
    (net (code "66") (name "/VBUS_B") (class "Default")
      (node (ref "U5") (pin "11") (pinfunction "VBUS_B_11") (pintype "passive"))
    )
    (net (code "67") (name "/VBUS_L") (class "Default")
      (node (ref "U5") (pin "16") (pinfunction "VBUS_L_16") (pintype "passive"))
    )
    (net (code "68") (name "/VOUT") (class "Default")
      (node (ref "C34") (pin "2") (pinfunction "2_2") (pintype "passive"))
      (node (ref "C35") (pin "2") (pinfunction "2_2") (pintype "passive"))
      (node (ref "C36") (pin "2") (pinfunction "2_2") (pintype "passive"))
      (node (ref "C37") (pin "1") (pinfunction "1_1") (pintype "passive"))
      (node (ref "R13") (pin "1") (pinfunction "1_1") (pintype "passive"))
      (node (ref "U5") (pin "28") (pinfunction "VOUT_SN_28") (pintype "passive"))
      (node (ref "U5") (pin "29") (pinfunction "VOUT_29") (pintype "passive"))
      (node (ref "U5") (pin "30") (pinfunction "VOUT_30") (pintype "passive"))
      (node (ref "U5") (pin "31") (pinfunction "VOUT_31") (pintype "passive"))
      (node (ref "U5") (pin "32") (pinfunction "VOUT_32") (pintype "passive"))
      (node (ref "U5") (pin "33") (pinfunction "VOUT_33") (pintype "passive"))
    )
    (net (code "69") (name "/VOUT_A1") (class "Default")
      (node (ref "C37") (pin "2") (pinfunction "2_2") (pintype "passive"))
      (node (ref "C38") (pin "2") (pinfunction "2_2") (pintype "passive"))
      (node (ref "C39") (pin "2") (pinfunction "2_2") (pintype "passive"))
      (node (ref "C40") (pin "2") (pinfunction "2_2") (pintype "passive"))
      (node (ref "R13") (pin "2") (pinfunction "2_2") (pintype "passive"))
      (node (ref "U4") (pin "2") (pinfunction "D_2") (pintype "passive"))
      (node (ref "U4") (pin "5") (pinfunction "D_5") (pintype "passive"))
      (node (ref "U5") (pin "13") (pinfunction "VOUT_C_13") (pintype "passive"))
      (node (ref "U5") (pin "14") (pinfunction "VOUT_A2_14") (pintype "passive"))
      (node (ref "U5") (pin "27") (pinfunction "VOUT_SP_27") (pintype "passive"))
      (node (ref "U5") (pin "9") (pinfunction "VOUT_A1_9") (pintype "passive"))
      (node (ref "U6") (pin "2") (pinfunction "D_2") (pintype "passive"))
      (node (ref "U6") (pin "5") (pinfunction "D_5") (pintype "passive"))
      (node (ref "U8") (pin "2") (pinfunction "D_2") (pintype "passive"))
      (node (ref "U8") (pin "5") (pinfunction "D_5") (pintype "passive"))
    )
    (net (code "70") (name "/WS2812_CTR1") (class "Default")
      (node (ref "R9") (pin "1") (pinfunction "1_1") (pintype "passive"))
      (node (ref "U1") (pin "58") (pinfunction "PB6_58") (pintype "passive"))
    )
    (net (code "71") (name "/WS2812_CTR2") (class "Default")
      (node (ref "R9") (pin "2") (pinfunction "2_2") (pintype "passive"))
      (node (ref "U1") (pin "59") (pinfunction "PB7_59") (pintype "passive"))
    )
    (net (code "72") (name "/WS2812_CTR3") (class "Default")
      (node (ref "R9") (pin "3") (pinfunction "3_3") (pintype "passive"))
      (node (ref "U1") (pin "61") (pinfunction "PB8_61") (pintype "passive"))
    )
    (net (code "73") (name "/nRST") (class "Default")
      (node (ref "C3") (pin "1") (pinfunction "1_1") (pintype "passive"))
      (node (ref "R8") (pin "1") (pinfunction "1_1") (pintype "passive"))
      (node (ref "RST1") (pin "1") (pinfunction "1_1") (pintype "passive"))
      (node (ref "U1") (pin "7") (pinfunction "NRST_7") (pintype "passive"))
    )
    (net (code "74") (name "AVCC3V3") (class "Default")
      (node (ref "C26") (pin "1") (pinfunction "1_1") (pintype "passive"))
      (node (ref "C27") (pin "1") (pinfunction "1_1") (pintype "passive"))
      (node (ref "R12") (pin "2") (pinfunction "2_2") (pintype "passive"))
      (node (ref "U1") (pin "13") (pinfunction "VDDA_13") (pintype "passive"))
    )
    (net (code "75") (name "BAT+") (class "Default")
      (node (ref "C29") (pin "2") (pinfunction "2_2") (pintype "passive"))
      (node (ref "C30") (pin "2") (pinfunction "2_2") (pintype "passive"))
      (node (ref "C31") (pin "2") (pinfunction "2_2") (pintype "passive"))
      (node (ref "C32") (pin "2") (pinfunction "2_2") (pintype "passive"))
      (node (ref "D7") (pin "2") (pinfunction "A_2") (pintype "passive"))
      (node (ref "L1") (pin "1") (pinfunction "1_1") (pintype "passive"))
      (node (ref "P4") (pin "1") (pinfunction "1_1") (pintype "passive"))
      (node (ref "P4") (pin "2") (pinfunction "2_2") (pintype "passive"))
      (node (ref "R32") (pin "1") (pinfunction "1_1") (pintype "passive"))
      (node (ref "U5") (pin "17") (pinfunction "BAT_17") (pintype "passive"))
    )
    (net (code "76") (name "BAT-") (class "Default")
      (node (ref "C54") (pin "1") (pinfunction "1_1") (pintype "passive"))
      (node (ref "P4") (pin "3") (pinfunction "3_3") (pintype "passive"))
      (node (ref "P4") (pin "4") (pinfunction "4_4") (pintype "passive"))
      (node (ref "U9") (pin "5") (pinfunction "GND_5") (pintype "passive"))
      (node (ref "U9") (pin "7") (pinfunction "GND_7") (pintype "passive"))
      (node (ref "U9") (pin "8") (pinfunction "GND_8") (pintype "passive"))
      (node (ref "U9") (pin "9") (pinfunction "PAD_9") (pintype "passive"))
    )
    (net (code "77") (name "GND") (class "Default")
      (node (ref "1") (pin "10") (pinfunction "10_10") (pintype "passive"))
      (node (ref "1") (pin "25") (pinfunction "25_25") (pintype "passive"))
      (node (ref "1") (pin "32") (pinfunction "32_32") (pintype "passive"))
      (node (ref "1") (pin "40") (pinfunction "40_40") (pintype "passive"))
      (node (ref "C1") (pin "2") (pinfunction "2_2") (pintype "passive"))
      (node (ref "C10") (pin "1") (pinfunction "1_1") (pintype "passive"))
      (node (ref "C11") (pin "1") (pinfunction "1_1") (pintype "passive"))
      (node (ref "C12") (pin "1") (pinfunction "1_1") (pintype "passive"))
      (node (ref "C13") (pin "2") (pinfunction "2_2") (pintype "passive"))
      (node (ref "C14") (pin "2") (pinfunction "2_2") (pintype "passive"))
      (node (ref "C15") (pin "2") (pinfunction "2_2") (pintype "passive"))
      (node (ref "C16") (pin "2") (pinfunction "2_2") (pintype "passive"))
      (node (ref "C17") (pin "1") (pinfunction "1_1") (pintype "passive"))
      (node (ref "C18") (pin "1") (pinfunction "1_1") (pintype "passive"))
      (node (ref "C19") (pin "2") (pinfunction "2_2") (pintype "passive"))
      (node (ref "C2") (pin "2") (pinfunction "2_2") (pintype "passive"))
      (node (ref "C20") (pin "2") (pinfunction "2_2") (pintype "passive"))
      (node (ref "C21") (pin "2") (pinfunction "2_2") (pintype "passive"))
      (node (ref "C22") (pin "2") (pinfunction "2_2") (pintype "passive"))
      (node (ref "C23") (pin "2") (pinfunction "2_2") (pintype "passive"))
      (node (ref "C24") (pin "2") (pinfunction "2_2") (pintype "passive"))
      (node (ref "C25") (pin "2") (pinfunction "2_2") (pintype "passive"))
      (node (ref "C26") (pin "2") (pinfunction "2_2") (pintype "passive"))
      (node (ref "C27") (pin "2") (pinfunction "2_2") (pintype "passive"))
      (node (ref "C28") (pin "1") (pinfunction "1_1") (pintype "passive"))
      (node (ref "C29") (pin "1") (pinfunction "1_1") (pintype "passive"))
      (node (ref "C3") (pin "2") (pinfunction "2_2") (pintype "passive"))
      (node (ref "C30") (pin "1") (pinfunction "1_1") (pintype "passive"))
      (node (ref "C31") (pin "1") (pinfunction "1_1") (pintype "passive"))
      (node (ref "C32") (pin "1") (pinfunction "1_1") (pintype "passive"))
      (node (ref "C34") (pin "1") (pinfunction "1_1") (pintype "passive"))
      (node (ref "C35") (pin "1") (pinfunction "1_1") (pintype "passive"))
      (node (ref "C36") (pin "1") (pinfunction "1_1") (pintype "passive"))
      (node (ref "C38") (pin "1") (pinfunction "1_1") (pintype "passive"))
      (node (ref "C39") (pin "1") (pinfunction "1_1") (pintype "passive"))
      (node (ref "C4") (pin "1") (pinfunction "1_1") (pintype "passive"))
      (node (ref "C40") (pin "1") (pinfunction "1_1") (pintype "passive"))
      (node (ref "C41") (pin "1") (pinfunction "1_1") (pintype "passive"))
      (node (ref "C42") (pin "2") (pinfunction "2_2") (pintype "passive"))
      (node (ref "C43") (pin "2") (pinfunction "2_2") (pintype "passive"))
      (node (ref "C44") (pin "2") (pinfunction "2_2") (pintype "passive"))
      (node (ref "C45") (pin "2") (pinfunction "2_2") (pintype "passive"))
      (node (ref "C46") (pin "1") (pinfunction "1_1") (pintype "passive"))
      (node (ref "C47") (pin "1") (pinfunction "1_1") (pintype "passive"))
      (node (ref "C48") (pin "1") (pinfunction "1_1") (pintype "passive"))
      (node (ref "C49") (pin "2") (pinfunction "2_2") (pintype "passive"))
      (node (ref "C5") (pin "1") (pinfunction "1_1") (pintype "passive"))
      (node (ref "C50") (pin "2") (pinfunction "2_2") (pintype "passive"))
      (node (ref "C51") (pin "2") (pinfunction "2_2") (pintype "passive"))
      (node (ref "C52") (pin "2") (pinfunction "2_2") (pintype "passive"))
      (node (ref "C53") (pin "2") (pinfunction "2_2") (pintype "passive"))
      (node (ref "C6") (pin "1") (pinfunction "1_1") (pintype "passive"))
      (node (ref "C7") (pin "1") (pinfunction "1_1") (pintype "passive"))
      (node (ref "C8") (pin "1") (pinfunction "1_1") (pintype "passive"))
      (node (ref "C9") (pin "1") (pinfunction "1_1") (pintype "passive"))
      (node (ref "D1") (pin "2") (pinfunction "K_2") (pintype "passive"))
      (node (ref "D2") (pin "2") (pinfunction "K_2") (pintype "passive"))
      (node (ref "D3") (pin "2") (pinfunction "K_2") (pintype "passive"))
      (node (ref "D4") (pin "2") (pinfunction "K_2") (pintype "passive"))
      (node (ref "D5") (pin "2") (pinfunction "K_2") (pintype "passive"))
      (node (ref "IC1") (pin "1") (pinfunction "GND_1_1") (pintype "passive"))
      (node (ref "IC1") (pin "40") (pinfunction "GND_2_40") (pintype "passive"))
      (node (ref "IC1") (pin "41") (pinfunction "GND_3_41") (pintype "passive"))
      (node (ref "IC1") (pin "42") (pinfunction "GND_4_42") (pintype "passive"))
      (node (ref "IC1") (pin "43") (pinfunction "GND_5_43") (pintype "passive"))
      (node (ref "IC1") (pin "44") (pinfunction "GND_6_44") (pintype "passive"))
      (node (ref "IC1") (pin "45") (pinfunction "GND_7_45") (pintype "passive"))
      (node (ref "IC1") (pin "46") (pinfunction "GND_8_46") (pintype "passive"))
      (node (ref "IC1") (pin "47") (pinfunction "GND_9_47") (pintype "passive"))
      (node (ref "IC1") (pin "48") (pinfunction "GND_10_48") (pintype "passive"))
      (node (ref "IC1") (pin "49") (pinfunction "GND_11_49") (pintype "passive"))
      (node (ref "IC2") (pin "5") (pinfunction "GND_TAB_5") (pintype "power_in"))
      (node (ref "P1") (pin "3") (pinfunction "3_3") (pintype "passive"))
      (node (ref "P2") (pin "1") (pinfunction "1_1") (pintype "passive"))
      (node (ref "P3") (pin "6") (pinfunction "6_6") (pintype "passive"))
      (node (ref "P4") (pin "6") (pinfunction "6_6") (pintype "passive"))
      (node (ref "R15") (pin "2") (pinfunction "2_2") (pintype "passive"))
      (node (ref "R23") (pin "2") (pinfunction "2_2") (pintype "passive"))
      (node (ref "R24") (pin "2") (pinfunction "2_2") (pintype "passive"))
      (node (ref "R25") (pin "1") (pinfunction "1_1") (pintype "passive"))
      (node (ref "R5") (pin "2") (pinfunction "2_2") (pintype "passive"))
      (node (ref "RST1") (pin "2") (pinfunction "2_2") (pintype "passive"))
      (node (ref "U1") (pin "12") (pinfunction "VSSA_12") (pintype "passive"))
      (node (ref "U1") (pin "18") (pinfunction "VSS_18") (pintype "passive"))
      (node (ref "U1") (pin "63") (pinfunction "VSS_63") (pintype "passive"))
      (node (ref "U2") (pin "2") (pinfunction "GND_2") (pintype "passive"))
      (node (ref "U3") (pin "2") (pinfunction "GND_2") (pintype "passive"))
      (node (ref "U5") (pin "49") (pinfunction "PAD_49") (pintype "passive"))
      (node (ref "U7") (pin "2") (pinfunction "GND_2") (pintype "passive"))
      (node (ref "U9") (pin "1") (pinfunction "VM_1") (pintype "passive"))
      (node (ref "U9") (pin "2") (pinfunction "VM_2") (pintype "passive"))
      (node (ref "U9") (pin "3") (pinfunction "VM_3") (pintype "passive"))
      (node (ref "U9") (pin "4") (pinfunction "VM_4") (pintype "passive"))
      (node (ref "USB1") (pin "A1") (pinfunction "GND_A1") (pintype "passive"))
      (node (ref "USB1") (pin "A12") (pinfunction "GND_A12") (pintype "passive"))
      (node (ref "USB1") (pin "B1") (pinfunction "GND_B1") (pintype "passive"))
      (node (ref "USB1") (pin "B12") (pinfunction "GND_B12") (pintype "passive"))
      (node (ref "X1") (pin "2") (pinfunction "2_2") (pintype "passive"))
      (node (ref "X1") (pin "4") (pinfunction "4_4") (pintype "passive"))
    )
    (net (code "78") (name "KEY_POS1") (class "Default")
      (node (ref "1") (pin "11") (pinfunction "11_11") (pintype "passive"))
      (node (ref "U1") (pin "8") (pinfunction "PC0_8") (pintype "passive"))
    )
    (net (code "79") (name "KEY_POS2") (class "Default")
      (node (ref "1") (pin "12") (pinfunction "12_12") (pintype "passive"))
      (node (ref "U1") (pin "9") (pinfunction "PC1_9") (pintype "passive"))
    )
    (net (code "80") (name "KEY_POS3") (class "Default")
      (node (ref "1") (pin "13") (pinfunction "13_13") (pintype "passive"))
      (node (ref "U1") (pin "10") (pinfunction "PC2_10") (pintype "passive"))
    )
    (net (code "81") (name "KEY_POS4") (class "Default")
      (node (ref "1") (pin "14") (pinfunction "14_14") (pintype "passive"))
      (node (ref "U1") (pin "11") (pinfunction "PC3_11") (pintype "passive"))
    )
    (net (code "82") (name "KEY_POS5") (class "Default")
      (node (ref "1") (pin "15") (pinfunction "15_15") (pintype "passive"))
      (node (ref "U1") (pin "24") (pinfunction "PC4_24") (pintype "passive"))
    )
    (net (code "83") (name "KEY_POS6") (class "Default")
      (node (ref "1") (pin "16") (pinfunction "16_16") (pintype "passive"))
      (node (ref "U1") (pin "25") (pinfunction "PC5_25") (pintype "passive"))
    )
    (net (code "84") (name "KEY_POS7") (class "Default")
      (node (ref "1") (pin "17") (pinfunction "17_17") (pintype "passive"))
      (node (ref "U1") (pin "37") (pinfunction "PC6_37") (pintype "passive"))
    )
    (net (code "85") (name "KEY_POS8") (class "Default")
      (node (ref "1") (pin "18") (pinfunction "18_18") (pintype "passive"))
      (node (ref "U1") (pin "38") (pinfunction "PC7_38") (pintype "passive"))
    )
    (net (code "86") (name "KEY_POS9") (class "Default")
      (node (ref "1") (pin "19") (pinfunction "19_19") (pintype "passive"))
      (node (ref "U1") (pin "39") (pinfunction "PC8_39") (pintype "passive"))
    )
    (net (code "87") (name "KEY_POS10") (class "Default")
      (node (ref "1") (pin "20") (pinfunction "20_20") (pintype "passive"))
      (node (ref "U1") (pin "53") (pinfunction "PC12_53") (pintype "passive"))
    )
    (net (code "88") (name "KEY_POS11") (class "Default")
      (node (ref "1") (pin "21") (pinfunction "21_21") (pintype "passive"))
      (node (ref "U1") (pin "54") (pinfunction "PD2_54") (pintype "passive"))
    )
    (net (code "89") (name "KEY_POS12") (class "Default")
      (node (ref "1") (pin "22") (pinfunction "22_22") (pintype "passive"))
      (node (ref "U1") (pin "2") (pinfunction "PC13_2") (pintype "passive"))
    )
    (net (code "90") (name "KEY_POS13") (class "Default")
      (node (ref "1") (pin "23") (pinfunction "23_23") (pintype "passive"))
      (node (ref "U1") (pin "3") (pinfunction "OSC32_IN/PC14_3") (pintype "passive"))
    )
    (net (code "91") (name "KEY_POS14") (class "Default")
      (node (ref "1") (pin "24") (pinfunction "24_24") (pintype "passive"))
      (node (ref "U1") (pin "4") (pinfunction "OSC32_OUT/PC15_4") (pintype "passive"))
    )
    (net (code "92") (name "KEY_SEG1") (class "Default")
      (node (ref "1") (pin "31") (pinfunction "31_31") (pintype "passive"))
      (node (ref "U1") (pin "27") (pinfunction "PB1_27") (pintype "passive"))
    )
    (net (code "93") (name "KEY_SEG2") (class "Default")
      (node (ref "1") (pin "30") (pinfunction "30_30") (pintype "passive"))
      (node (ref "U1") (pin "29") (pinfunction "PB10_29") (pintype "passive"))
    )
    (net (code "94") (name "KEY_SEG3") (class "Default")
      (node (ref "1") (pin "29") (pinfunction "29_29") (pintype "passive"))
      (node (ref "U1") (pin "30") (pinfunction "PB11_30") (pintype "passive"))
    )
    (net (code "95") (name "KEY_SEG4") (class "Default")
      (node (ref "1") (pin "28") (pinfunction "28_28") (pintype "passive"))
      (node (ref "U1") (pin "33") (pinfunction "PB12_33") (pintype "passive"))
    )
    (net (code "96") (name "KEY_SEG5") (class "Default")
      (node (ref "1") (pin "27") (pinfunction "27_27") (pintype "passive"))
      (node (ref "U1") (pin "34") (pinfunction "PB13_34") (pintype "passive"))
    )
    (net (code "97") (name "KEY_SEG6") (class "Default")
      (node (ref "1") (pin "26") (pinfunction "26_26") (pintype "passive"))
      (node (ref "U1") (pin "35") (pinfunction "PB14_35") (pintype "passive"))
    )
    (net (code "98") (name "Net-(1-Pad35)") (class "Default")
      (node (ref "1") (pin "35") (pinfunction "35_35") (pintype "passive"))
      (node (ref "R1") (pin "5") (pinfunction "5_5") (pintype "passive"))
    )
    (net (code "99") (name "Net-(1-Pad36)") (class "Default")
      (node (ref "1") (pin "36") (pinfunction "36_36") (pintype "passive"))
      (node (ref "R1") (pin "6") (pinfunction "6_6") (pintype "passive"))
    )
    (net (code "100") (name "Net-(1-Pad37)") (class "Default")
      (node (ref "1") (pin "37") (pinfunction "37_37") (pintype "passive"))
      (node (ref "R1") (pin "7") (pinfunction "7_7") (pintype "passive"))
    )
    (net (code "101") (name "Net-(1-Pad38)") (class "Default")
      (node (ref "1") (pin "38") (pinfunction "38_38") (pintype "passive"))
      (node (ref "R1") (pin "8") (pinfunction "8_8") (pintype "passive"))
    )
    (net (code "102") (name "Net-(D1-A)") (class "Default")
      (node (ref "1") (pin "9") (pinfunction "9_9") (pintype "passive"))
      (node (ref "C8") (pin "2") (pinfunction "2_2") (pintype "passive"))
      (node (ref "D1") (pin "1") (pinfunction "A_1") (pintype "passive"))
      (node (ref "R9") (pin "8") (pinfunction "8_8") (pintype "passive"))
    )
    (net (code "103") (name "Net-(D2-A)") (class "Default")
      (node (ref "1") (pin "8") (pinfunction "8_8") (pintype "passive"))
      (node (ref "C9") (pin "2") (pinfunction "2_2") (pintype "passive"))
      (node (ref "D2") (pin "1") (pinfunction "A_1") (pintype "passive"))
      (node (ref "R9") (pin "7") (pinfunction "7_7") (pintype "passive"))
    )
    (net (code "104") (name "Net-(D3-A)") (class "Default")
      (node (ref "1") (pin "7") (pinfunction "7_7") (pintype "passive"))
      (node (ref "C10") (pin "2") (pinfunction "2_2") (pintype "passive"))
      (node (ref "D3") (pin "1") (pinfunction "A_1") (pintype "passive"))
      (node (ref "R9") (pin "6") (pinfunction "6_6") (pintype "passive"))
    )
    (net (code "105") (name "Net-(D6-K)") (class "Default")
      (node (ref "D6") (pin "1") (pinfunction "K_1") (pintype "passive"))
      (node (ref "D7") (pin "1") (pinfunction "K_1") (pintype "passive"))
      (node (ref "R26") (pin "1") (pinfunction "1_1") (pintype "passive"))
    )
    (net (code "106") (name "Net-(F1-Pad2)") (class "Default")
      (node (ref "F1") (pin "2") (pinfunction "2_2") (pintype "passive"))
      (node (ref "P1") (pin "4") (pinfunction "4_4") (pintype "passive"))
    )
    (net (code "107") (name "Net-(IC2-SENSE)") (class "Default")
      (node (ref "IC2") (pin "4") (pinfunction "SENSE_4") (pintype "passive"))
      (node (ref "R28") (pin "1") (pinfunction "1_1") (pintype "passive"))
    )
    (net (code "108") (name "Net-(IC2-~{SD})") (class "Default")
      (node (ref "IC2") (pin "1") (pinfunction "~{SD}_1") (pintype "passive"))
      (node (ref "R25") (pin "2") (pinfunction "2_2") (pintype "passive"))
      (node (ref "R27") (pin "2") (pinfunction "2_2") (pintype "passive"))
    )
    (net (code "109") (name "Net-(P1-Pad1)") (class "Default")
      (node (ref "P1") (pin "1") (pinfunction "1_1") (pintype "passive"))
      (node (ref "R2") (pin "2") (pinfunction "2_2") (pintype "passive"))
    )
    (net (code "110") (name "Net-(P1-Pad2)") (class "Default")
      (node (ref "P1") (pin "2") (pinfunction "2_2") (pintype "passive"))
      (node (ref "R3") (pin "2") (pinfunction "2_2") (pintype "passive"))
    )
    (net (code "111") (name "Net-(P3-Pad2)") (class "Default")
      (node (ref "P3") (pin "2") (pinfunction "2_2") (pintype "passive"))
      (node (ref "R20") (pin "1") (pinfunction "1_1") (pintype "passive"))
    )
    (net (code "112") (name "Net-(P3-Pad3)") (class "Default")
      (node (ref "P3") (pin "3") (pinfunction "3_3") (pintype "passive"))
      (node (ref "R20") (pin "2") (pinfunction "2_2") (pintype "passive"))
    )
    (net (code "113") (name "Net-(P3-Pad4)") (class "Default")
      (node (ref "P3") (pin "4") (pinfunction "4_4") (pintype "passive"))
      (node (ref "R20") (pin "3") (pinfunction "3_3") (pintype "passive"))
    )
    (net (code "114") (name "Net-(P3-Pad5)") (class "Default")
      (node (ref "P3") (pin "5") (pinfunction "5_5") (pintype "passive"))
      (node (ref "R20") (pin "4") (pinfunction "4_4") (pintype "passive"))
    )
    (net (code "115") (name "Net-(Q1-B)") (class "Default")
      (node (ref "Q1") (pin "1") (pinfunction "B_1") (pintype "passive"))
      (node (ref "R4") (pin "2") (pinfunction "2_2") (pintype "passive"))
      (node (ref "R6") (pin "1") (pinfunction "1_1") (pintype "passive"))
    )
    (net (code "116") (name "Net-(Q1-C)") (class "Default")
      (node (ref "Q1") (pin "3") (pinfunction "C_3") (pintype "passive"))
      (node (ref "R7") (pin "2") (pinfunction "2_2") (pintype "passive"))
    )
    (net (code "117") (name "Net-(R14-Pad2)") (class "Default")
      (node (ref "R14") (pin "2") (pinfunction "2_2") (pintype "passive"))
      (node (ref "R15") (pin "1") (pinfunction "1_1") (pintype "passive"))
      (node (ref "U7") (pin "3") (pinfunction "EN_3") (pintype "passive"))
    )
    (net (code "118") (name "Net-(U1-RCC_OSC_IN{slash}PH0)") (class "Default")
      (node (ref "C1") (pin "1") (pinfunction "1_1") (pintype "passive"))
      (node (ref "U1") (pin "5") (pinfunction "RCC_OSC_IN/PH0_5") (pintype "passive"))
      (node (ref "X1") (pin "3") (pinfunction "3_3") (pintype "passive"))
    )
    (net (code "119") (name "Net-(U1-RCC_OSC_OUT{slash}PH1)") (class "Default")
      (node (ref "C2") (pin "1") (pinfunction "1_1") (pintype "passive"))
      (node (ref "U1") (pin "6") (pinfunction "RCC_OSC_OUT/PH1_6") (pintype "passive"))
      (node (ref "X1") (pin "1") (pinfunction "1_1") (pintype "passive"))
    )
    (net (code "120") (name "Net-(U1-VCAP_1)") (class "Default")
      (node (ref "C17") (pin "2") (pinfunction "2_2") (pintype "passive"))
      (node (ref "U1") (pin "31") (pinfunction "VCAP_1_31") (pintype "passive"))
    )
    (net (code "121") (name "Net-(U1-VCAP_2)") (class "Default")
      (node (ref "C18") (pin "2") (pinfunction "2_2") (pintype "passive"))
      (node (ref "U1") (pin "47") (pinfunction "VCAP_2_47") (pintype "passive"))
    )
    (net (code "122") (name "Net-(U9-VDD)") (class "Default")
      (node (ref "C54") (pin "2") (pinfunction "2_2") (pintype "passive"))
      (node (ref "R32") (pin "2") (pinfunction "2_2") (pintype "passive"))
      (node (ref "U9") (pin "6") (pinfunction "VDD_6") (pintype "passive"))
    )
    (net (code "123") (name "USBVCC") (class "Default")
      (node (ref "C28") (pin "2") (pinfunction "2_2") (pintype "passive"))
      (node (ref "U4") (pin "1") (pinfunction "S1_1") (pintype "passive"))
      (node (ref "U4") (pin "3") (pinfunction "S2_3") (pintype "passive"))
      (node (ref "U5") (pin "12") (pinfunction "VBUS_C_12") (pintype "passive"))
      (node (ref "USB1") (pin "A4") (pinfunction "VBUS_A4") (pintype "passive"))
      (node (ref "USB1") (pin "A9") (pinfunction "VBUS_A9") (pintype "passive"))
      (node (ref "USB1") (pin "B4") (pinfunction "VBUS_B4") (pintype "passive"))
      (node (ref "USB1") (pin "B9") (pinfunction "VBUS_B9") (pintype "passive"))
    )
    (net (code "124") (name "VCC") (class "Default")
      (node (ref "D6") (pin "2") (pinfunction "A_2") (pintype "passive"))
      (node (ref "R21") (pin "2") (pinfunction "2_2") (pintype "passive"))
      (node (ref "R22") (pin "2") (pinfunction "2_2") (pintype "passive"))
      (node (ref "U5") (pin "19") (pinfunction "VCC_19") (pintype "passive"))
    )
    (net (code "125") (name "VCC3V3") (class "Default")
      (node (ref "C11") (pin "2") (pinfunction "2_2") (pintype "passive"))
      (node (ref "C12") (pin "2") (pinfunction "2_2") (pintype "passive"))
      (node (ref "C24") (pin "1") (pinfunction "1_1") (pintype "passive"))
      (node (ref "C25") (pin "1") (pinfunction "1_1") (pintype "passive"))
      (node (ref "C4") (pin "2") (pinfunction "2_2") (pintype "passive"))
      (node (ref "C5") (pin "2") (pinfunction "2_2") (pintype "passive"))
      (node (ref "C6") (pin "2") (pinfunction "2_2") (pintype "passive"))
      (node (ref "C7") (pin "2") (pinfunction "2_2") (pintype "passive"))
      (node (ref "F1") (pin "1") (pinfunction "1_1") (pintype "passive"))
      (node (ref "R12") (pin "1") (pinfunction "1_1") (pintype "passive"))
      (node (ref "R16") (pin "1") (pinfunction "1_1") (pintype "passive"))
      (node (ref "R17") (pin "1") (pinfunction "1_1") (pintype "passive"))
      (node (ref "R18") (pin "1") (pinfunction "1_1") (pintype "passive"))
      (node (ref "R8") (pin "2") (pinfunction "2_2") (pintype "passive"))
      (node (ref "U1") (pin "1") (pinfunction "VBAT_1") (pintype "passive"))
      (node (ref "U1") (pin "19") (pinfunction "VDD_19") (pintype "passive"))
      (node (ref "U1") (pin "32") (pinfunction "VDD_32") (pintype "passive"))
      (node (ref "U1") (pin "48") (pinfunction "VDD_48") (pintype "passive"))
      (node (ref "U1") (pin "64") (pinfunction "VDD_64") (pintype "passive"))
      (node (ref "U3") (pin "5") (pinfunction "VOUT_5") (pintype "passive"))
    )
    (net (code "126") (name "VCC3V3_1A") (class "Default")
      (node (ref "1") (pin "33") (pinfunction "33_33") (pintype "passive"))
      (node (ref "C52") (pin "1") (pinfunction "1_1") (pintype "passive"))
      (node (ref "C53") (pin "1") (pinfunction "1_1") (pintype "passive"))
      (node (ref "IC2") (pin "3") (pinfunction "OUT_3") (pintype "output"))
      (node (ref "R28") (pin "2") (pinfunction "2_2") (pintype "passive"))
    )
    (net (code "127") (name "VCC_BLE") (class "Default")
      (node (ref "C15") (pin "1") (pinfunction "1_1") (pintype "passive"))
      (node (ref "C16") (pin "1") (pinfunction "1_1") (pintype "passive"))
      (node (ref "C47") (pin "2") (pinfunction "2_2") (pintype "passive"))
      (node (ref "C48") (pin "2") (pinfunction "2_2") (pintype "passive"))
      (node (ref "IC1") (pin "2") (pinfunction "3V3_2") (pintype "passive"))
      (node (ref "P3") (pin "1") (pinfunction "1_1") (pintype "passive"))
      (node (ref "R19") (pin "2") (pinfunction "2_2") (pintype "passive"))
      (node (ref "U2") (pin "5") (pinfunction "VOUT_5") (pintype "passive"))
    )
    (net (code "128") (name "VCC_BUS") (class "Default")
      (node (ref "C13") (pin "1") (pinfunction "1_1") (pintype "passive"))
      (node (ref "C14") (pin "1") (pinfunction "1_1") (pintype "passive"))
      (node (ref "C22") (pin "1") (pinfunction "1_1") (pintype "passive"))
      (node (ref "C23") (pin "1") (pinfunction "1_1") (pintype "passive"))
      (node (ref "C42") (pin "1") (pinfunction "1_1") (pintype "passive"))
      (node (ref "C43") (pin "1") (pinfunction "1_1") (pintype "passive"))
      (node (ref "C50") (pin "1") (pinfunction "1_1") (pintype "passive"))
      (node (ref "C51") (pin "1") (pinfunction "1_1") (pintype "passive"))
      (node (ref "IC2") (pin "2") (pinfunction "IN_2") (pintype "input"))
      (node (ref "R26") (pin "2") (pinfunction "2_2") (pintype "passive"))
      (node (ref "U2") (pin "1") (pinfunction "EN_1") (pintype "passive"))
      (node (ref "U3") (pin "1") (pinfunction "EN_1") (pintype "passive"))
      (node (ref "U3") (pin "3") (pinfunction "EN_3") (pintype "passive"))
      (node (ref "U7") (pin "1") (pinfunction "EN_1") (pintype "passive"))
    )
    (net (code "129") (name "VCC_LCD") (class "Default")
      (node (ref "1") (pin "39") (pinfunction "39_39") (pintype "passive"))
      (node (ref "C44") (pin "1") (pinfunction "1_1") (pintype "passive"))
      (node (ref "C45") (pin "1") (pinfunction "1_1") (pintype "passive"))
      (node (ref "P2") (pin "4") (pinfunction "4_4") (pintype "passive"))
      (node (ref "P2") (pin "6") (pinfunction "6_6") (pintype "passive"))
      (node (ref "Q1") (pin "2") (pinfunction "E_2") (pintype "passive"))
      (node (ref "R6") (pin "2") (pinfunction "2_2") (pintype "passive"))
      (node (ref "U7") (pin "5") (pinfunction "VOUT_5") (pintype "passive"))
    )
    (net (code "130") (name "unconnected-(IC1-IO1-Pad39)") (class "Default")
      (node (ref "IC1") (pin "39") (pinfunction "IO1_39") (pintype "passive+no_connect"))
    )
    (net (code "131") (name "unconnected-(IC1-IO2-Pad38)") (class "Default")
      (node (ref "IC1") (pin "38") (pinfunction "IO2_38") (pintype "passive+no_connect"))
    )
    (net (code "132") (name "unconnected-(IC1-IO3-Pad15)") (class "Default")
      (node (ref "IC1") (pin "15") (pinfunction "IO3_15") (pintype "passive+no_connect"))
    )
    (net (code "133") (name "unconnected-(IC1-IO4-Pad4)") (class "Default")
      (node (ref "IC1") (pin "4") (pinfunction "IO4_4") (pintype "passive+no_connect"))
    )
    (net (code "134") (name "unconnected-(IC1-IO5-Pad5)") (class "Default")
      (node (ref "IC1") (pin "5") (pinfunction "IO5_5") (pintype "passive+no_connect"))
    )
    (net (code "135") (name "unconnected-(IC1-IO6-Pad6)") (class "Default")
      (node (ref "IC1") (pin "6") (pinfunction "IO6_6") (pintype "passive+no_connect"))
    )
    (net (code "136") (name "unconnected-(IC1-IO7-Pad7)") (class "Default")
      (node (ref "IC1") (pin "7") (pinfunction "IO7_7") (pintype "passive+no_connect"))
    )
    (net (code "137") (name "unconnected-(IC1-IO8-Pad12)") (class "Default")
      (node (ref "IC1") (pin "12") (pinfunction "IO8_12") (pintype "passive+no_connect"))
    )
    (net (code "138") (name "unconnected-(IC1-IO9-Pad17)") (class "Default")
      (node (ref "IC1") (pin "17") (pinfunction "IO9_17") (pintype "passive+no_connect"))
    )
    (net (code "139") (name "unconnected-(IC1-IO10-Pad18)") (class "Default")
      (node (ref "IC1") (pin "18") (pinfunction "IO10_18") (pintype "passive+no_connect"))
    )
    (net (code "140") (name "unconnected-(IC1-IO11-Pad19)") (class "Default")
      (node (ref "IC1") (pin "19") (pinfunction "IO11_19") (pintype "passive+no_connect"))
    )
    (net (code "141") (name "unconnected-(IC1-IO12-Pad20)") (class "Default")
      (node (ref "IC1") (pin "20") (pinfunction "IO12_20") (pintype "passive+no_connect"))
    )
    (net (code "142") (name "unconnected-(IC1-IO13-Pad21)") (class "Default")
      (node (ref "IC1") (pin "21") (pinfunction "IO13_21") (pintype "passive+no_connect"))
    )
    (net (code "143") (name "unconnected-(IC1-IO14-Pad22)") (class "Default")
      (node (ref "IC1") (pin "22") (pinfunction "IO14_22") (pintype "passive+no_connect"))
    )
    (net (code "144") (name "unconnected-(IC1-IO15-Pad8)") (class "Default")
      (node (ref "IC1") (pin "8") (pinfunction "IO15_8") (pintype "passive+no_connect"))
    )
    (net (code "145") (name "unconnected-(IC1-IO16-Pad9)") (class "Default")
      (node (ref "IC1") (pin "9") (pinfunction "IO16_9") (pintype "passive+no_connect"))
    )
    (net (code "146") (name "unconnected-(IC1-IO19-Pad13)") (class "Default")
      (node (ref "IC1") (pin "13") (pinfunction "IO19_13") (pintype "passive+no_connect"))
    )
    (net (code "147") (name "unconnected-(IC1-IO20-Pad14)") (class "Default")
      (node (ref "IC1") (pin "14") (pinfunction "IO20_14") (pintype "passive+no_connect"))
    )
    (net (code "148") (name "unconnected-(IC1-IO21-Pad23)") (class "Default")
      (node (ref "IC1") (pin "23") (pinfunction "IO21_23") (pintype "passive+no_connect"))
    )
    (net (code "149") (name "unconnected-(IC1-IO35-Pad28)") (class "Default")
      (node (ref "IC1") (pin "28") (pinfunction "IO35_28") (pintype "passive+no_connect"))
    )
    (net (code "150") (name "unconnected-(IC1-IO36-Pad29)") (class "Default")
      (node (ref "IC1") (pin "29") (pinfunction "IO36_29") (pintype "passive+no_connect"))
    )
    (net (code "151") (name "unconnected-(IC1-IO37-Pad30)") (class "Default")
      (node (ref "IC1") (pin "30") (pinfunction "IO37_30") (pintype "passive+no_connect"))
    )
    (net (code "152") (name "unconnected-(IC1-IO38-Pad31)") (class "Default")
      (node (ref "IC1") (pin "31") (pinfunction "IO38_31") (pintype "passive+no_connect"))
    )
    (net (code "153") (name "unconnected-(IC1-IO39-Pad32)") (class "Default")
      (node (ref "IC1") (pin "32") (pinfunction "IO39_32") (pintype "passive+no_connect"))
    )
    (net (code "154") (name "unconnected-(IC1-IO40-Pad33)") (class "Default")
      (node (ref "IC1") (pin "33") (pinfunction "IO40_33") (pintype "passive+no_connect"))
    )
    (net (code "155") (name "unconnected-(IC1-IO41-Pad34)") (class "Default")
      (node (ref "IC1") (pin "34") (pinfunction "IO41_34") (pintype "passive+no_connect"))
    )
    (net (code "156") (name "unconnected-(IC1-IO42-Pad35)") (class "Default")
      (node (ref "IC1") (pin "35") (pinfunction "IO42_35") (pintype "passive+no_connect"))
    )
    (net (code "157") (name "unconnected-(IC1-IO45-Pad26)") (class "Default")
      (node (ref "IC1") (pin "26") (pinfunction "IO45_26") (pintype "passive+no_connect"))
    )
    (net (code "158") (name "unconnected-(IC1-IO46-Pad16)") (class "Default")
      (node (ref "IC1") (pin "16") (pinfunction "IO46_16") (pintype "passive+no_connect"))
    )
    (net (code "159") (name "unconnected-(IC1-IO47-Pad24)") (class "Default")
      (node (ref "IC1") (pin "24") (pinfunction "IO47_24") (pintype "passive+no_connect"))
    )
    (net (code "160") (name "unconnected-(IC1-IO48-Pad25)") (class "Default")
      (node (ref "IC1") (pin "25") (pinfunction "IO48_25") (pintype "passive+no_connect"))
    )
    (net (code "161") (name "unconnected-(P1-PadMP1)") (class "Default")
      (node (ref "P1") (pin "MP1") (pinfunction "MP1_MP1") (pintype "passive+no_connect"))
    )
    (net (code "162") (name "unconnected-(P1-PadMP2)") (class "Default")
      (node (ref "P1") (pin "MP2") (pinfunction "MP2_MP2") (pintype "passive+no_connect"))
    )
    (net (code "163") (name "unconnected-(P2-PadMP1)") (class "Default")
      (node (ref "P2") (pin "MP1") (pinfunction "MP1_MP1") (pintype "passive+no_connect"))
    )
    (net (code "164") (name "unconnected-(P2-PadMP2)") (class "Default")
      (node (ref "P2") (pin "MP2") (pinfunction "MP2_MP2") (pintype "passive+no_connect"))
    )
    (net (code "165") (name "unconnected-(P3-PadMP1)") (class "Default")
      (node (ref "P3") (pin "MP1") (pinfunction "MP1_MP1") (pintype "passive+no_connect"))
    )
    (net (code "166") (name "unconnected-(P3-PadMP2)") (class "Default")
      (node (ref "P3") (pin "MP2") (pinfunction "MP2_MP2") (pintype "passive+no_connect"))
    )
    (net (code "167") (name "unconnected-(P4-PadMP1)") (class "Default")
      (node (ref "P4") (pin "MP1") (pinfunction "MP1_MP1") (pintype "passive+no_connect"))
    )
    (net (code "168") (name "unconnected-(P4-PadMP2)") (class "Default")
      (node (ref "P4") (pin "MP2") (pinfunction "MP2_MP2") (pintype "passive+no_connect"))
    )
    (net (code "169") (name "unconnected-(R9-Pad4)") (class "Default")
      (node (ref "R9") (pin "4") (pinfunction "4_4") (pintype "passive"))
    )
    (net (code "170") (name "unconnected-(R9-Pad5)") (class "Default")
      (node (ref "R9") (pin "5") (pinfunction "5_5") (pintype "passive"))
    )
    (net (code "171") (name "unconnected-(R33-Pad2)") (class "Default")
      (node (ref "R33") (pin "2") (pinfunction "2_2") (pintype "passive+no_connect"))
    )
    (net (code "172") (name "unconnected-(R34-Pad2)") (class "Default")
      (node (ref "R34") (pin "2") (pinfunction "2_2") (pintype "passive+no_connect"))
    )
    (net (code "173") (name "unconnected-(U2-NC-Pad4)") (class "Default")
      (node (ref "U2") (pin "4") (pinfunction "NC_4") (pintype "passive+no_connect"))
    )
    (net (code "174") (name "unconnected-(U3-NC-Pad4)") (class "Default")
      (node (ref "U3") (pin "4") (pinfunction "NC_4") (pintype "passive+no_connect"))
    )
    (net (code "175") (name "unconnected-(U7-NC-Pad4)") (class "Default")
      (node (ref "U7") (pin "4") (pinfunction "NC_4") (pintype "passive+no_connect"))
    )
    (net (code "176") (name "unconnected-(USB1-RX1+-PadB11)") (class "Default")
      (node (ref "USB1") (pin "B11") (pinfunction "RX1+_B11") (pintype "passive+no_connect"))
    )
    (net (code "177") (name "unconnected-(USB1-RX1--PadB10)") (class "Default")
      (node (ref "USB1") (pin "B10") (pinfunction "RX1-_B10") (pintype "passive+no_connect"))
    )
    (net (code "178") (name "unconnected-(USB1-RX2+-PadA11)") (class "Default")
      (node (ref "USB1") (pin "A11") (pinfunction "RX2+_A11") (pintype "passive+no_connect"))
    )
    (net (code "179") (name "unconnected-(USB1-RX2--PadA10)") (class "Default")
      (node (ref "USB1") (pin "A10") (pinfunction "RX2-_A10") (pintype "passive+no_connect"))
    )
    (net (code "180") (name "unconnected-(USB1-SBU1-PadA8)") (class "Default")
      (node (ref "USB1") (pin "A8") (pinfunction "SBU1_A8") (pintype "passive+no_connect"))
    )
    (net (code "181") (name "unconnected-(USB1-SBU2-PadB8)") (class "Default")
      (node (ref "USB1") (pin "B8") (pinfunction "SBU2_B8") (pintype "passive+no_connect"))
    )
    (net (code "182") (name "unconnected-(USB1-SH1-Pad1)") (class "Default")
      (node (ref "USB1") (pin "1") (pinfunction "SH1_1") (pintype "passive+no_connect"))
    )
    (net (code "183") (name "unconnected-(USB1-SH2-Pad2)") (class "Default")
      (node (ref "USB1") (pin "2") (pinfunction "SH2_2") (pintype "passive+no_connect"))
    )
    (net (code "184") (name "unconnected-(USB1-SH3-Pad3)") (class "Default")
      (node (ref "USB1") (pin "3") (pinfunction "SH3_3") (pintype "passive+no_connect"))
    )
    (net (code "185") (name "unconnected-(USB1-SH4-Pad4)") (class "Default")
      (node (ref "USB1") (pin "4") (pinfunction "SH4_4") (pintype "passive+no_connect"))
    )
    (net (code "186") (name "unconnected-(USB1-TX1+-PadA2)") (class "Default")
      (node (ref "USB1") (pin "A2") (pinfunction "TX1+_A2") (pintype "passive+no_connect"))
    )
    (net (code "187") (name "unconnected-(USB1-TX1--PadA3)") (class "Default")
      (node (ref "USB1") (pin "A3") (pinfunction "TX1-_A3") (pintype "passive+no_connect"))
    )
    (net (code "188") (name "unconnected-(USB1-TX2+-PadB2)") (class "Default")
      (node (ref "USB1") (pin "B2") (pinfunction "TX2+_B2") (pintype "passive+no_connect"))
    )
    (net (code "189") (name "unconnected-(USB1-TX2--PadB3)") (class "Default")
      (node (ref "USB1") (pin "B3") (pinfunction "TX2-_B3") (pintype "passive+no_connect"))
    )
  )
)
